# ProProject_Spherical_Robot_RC_V2_0_2024-.net
KiCad netlist of a schematic drawn in EasyEDA Pro
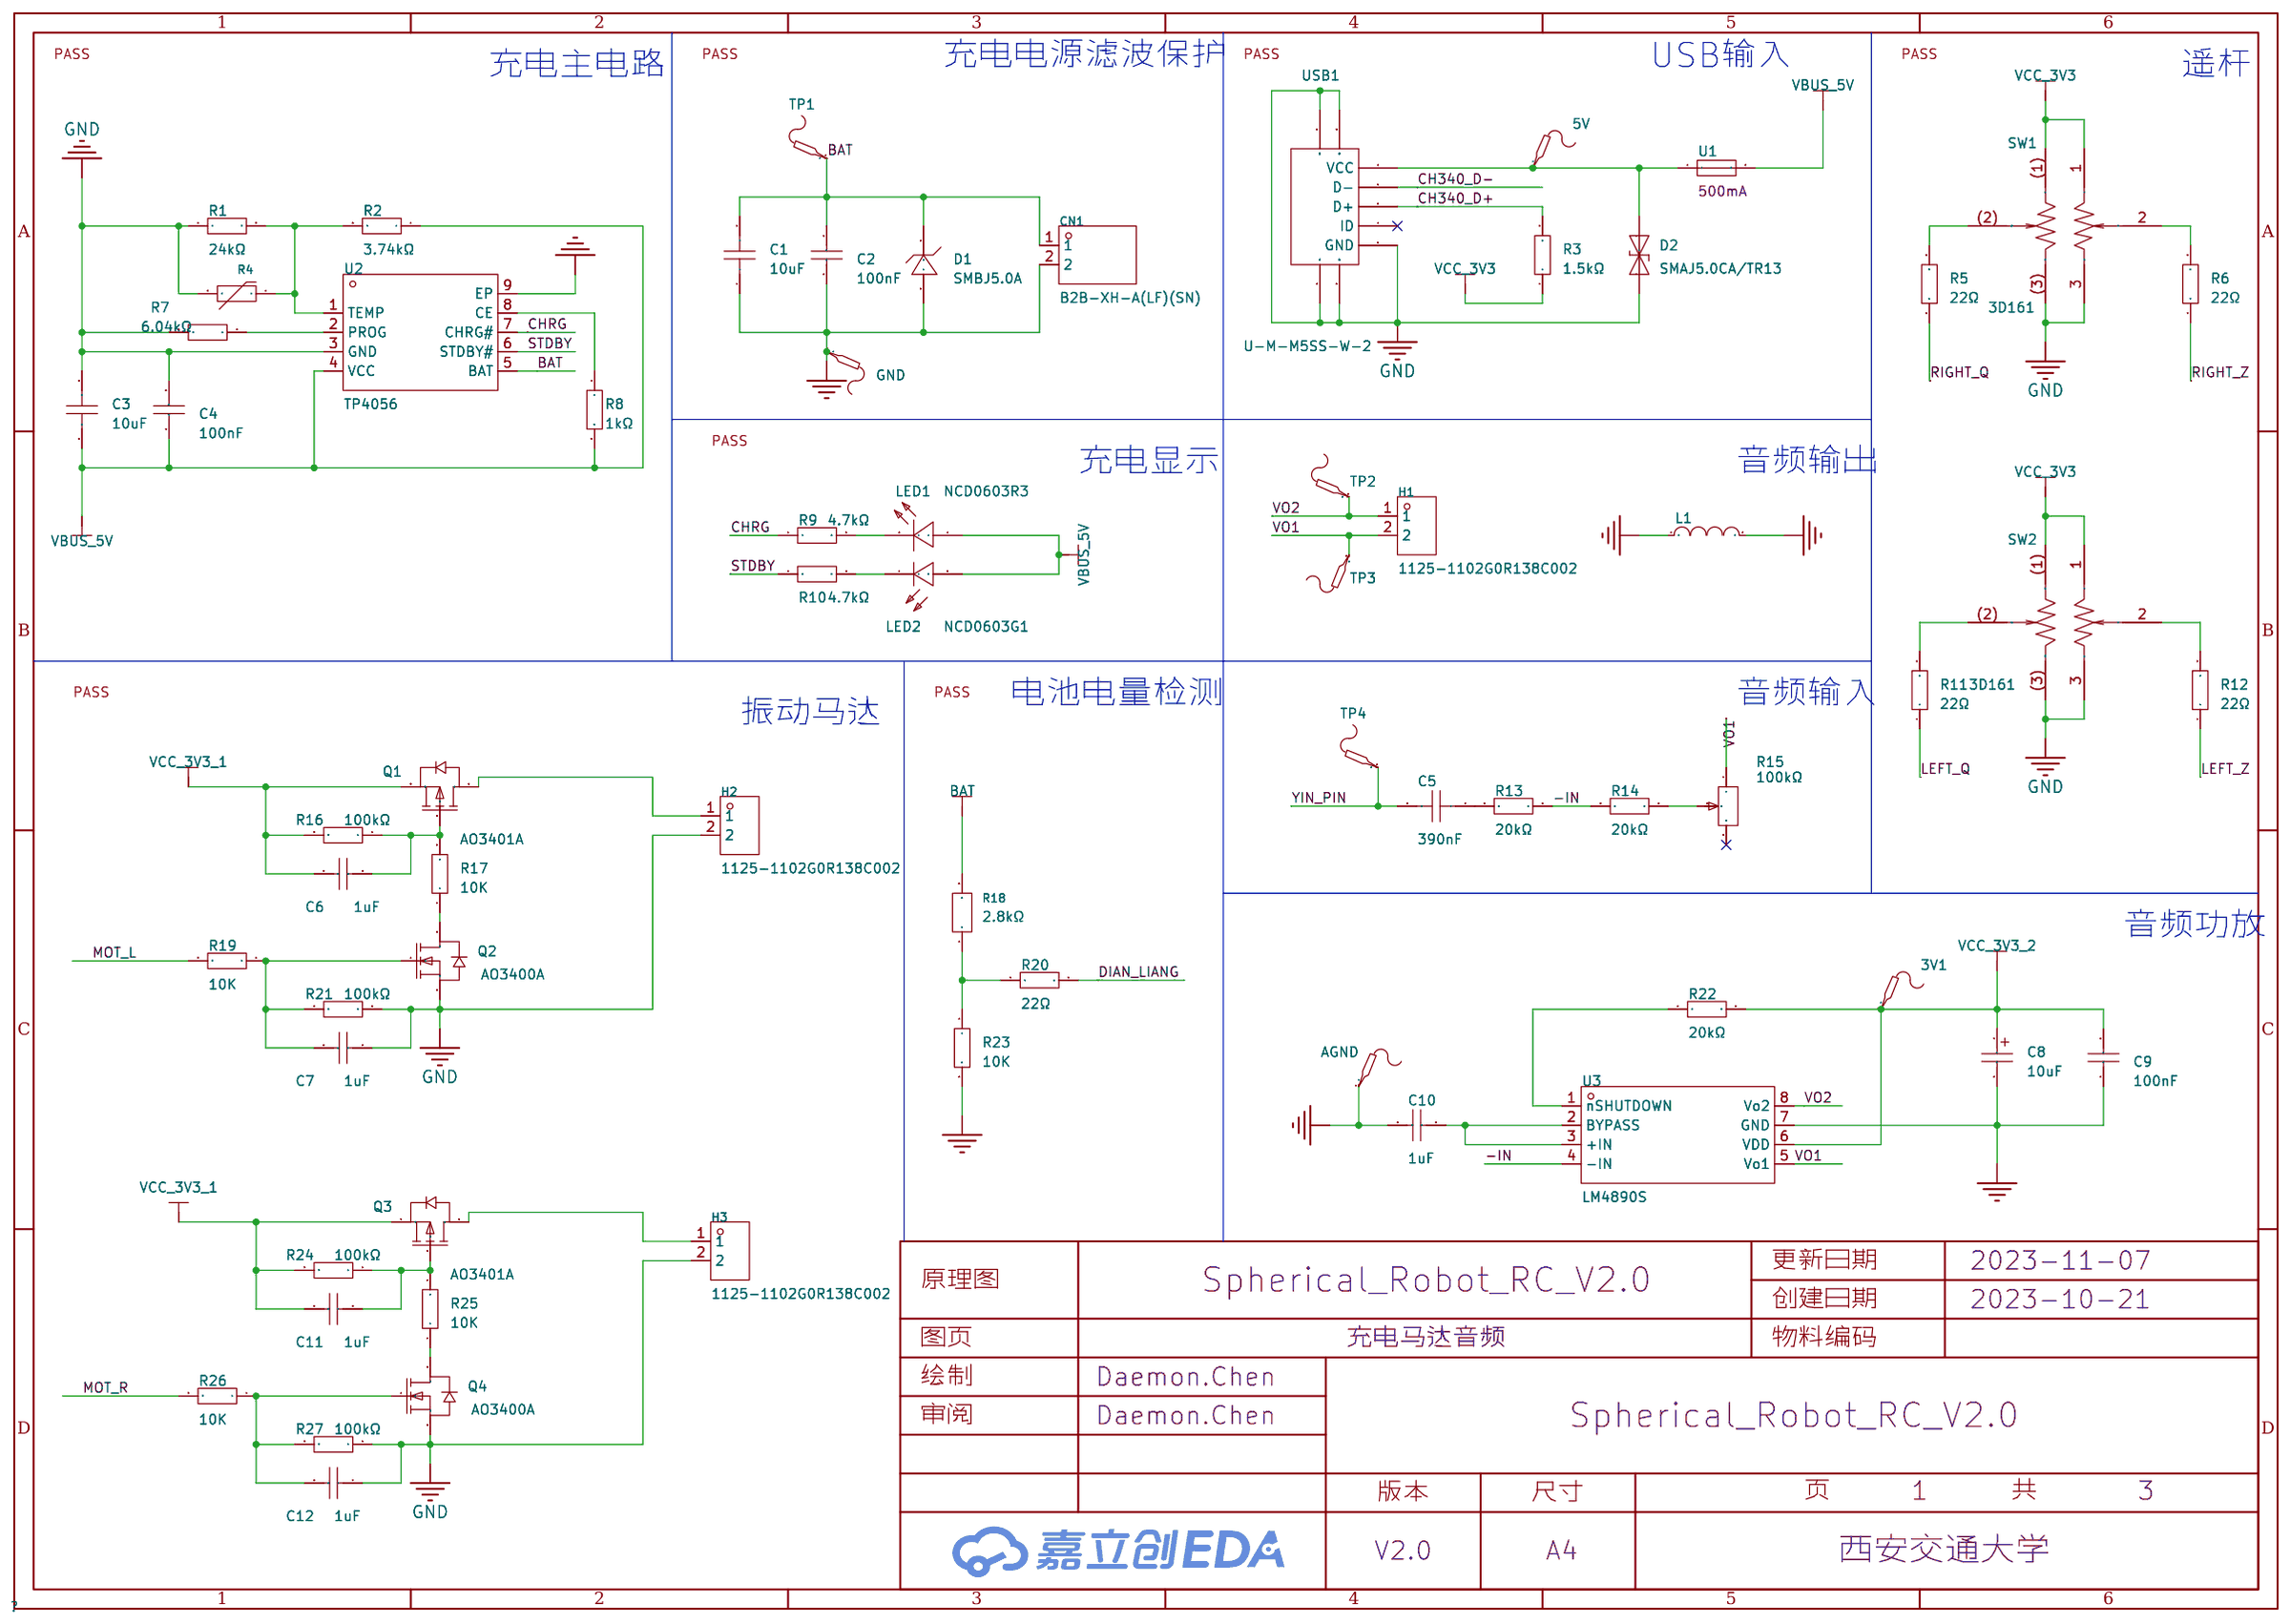
[diagram p0: 充电马达音频]
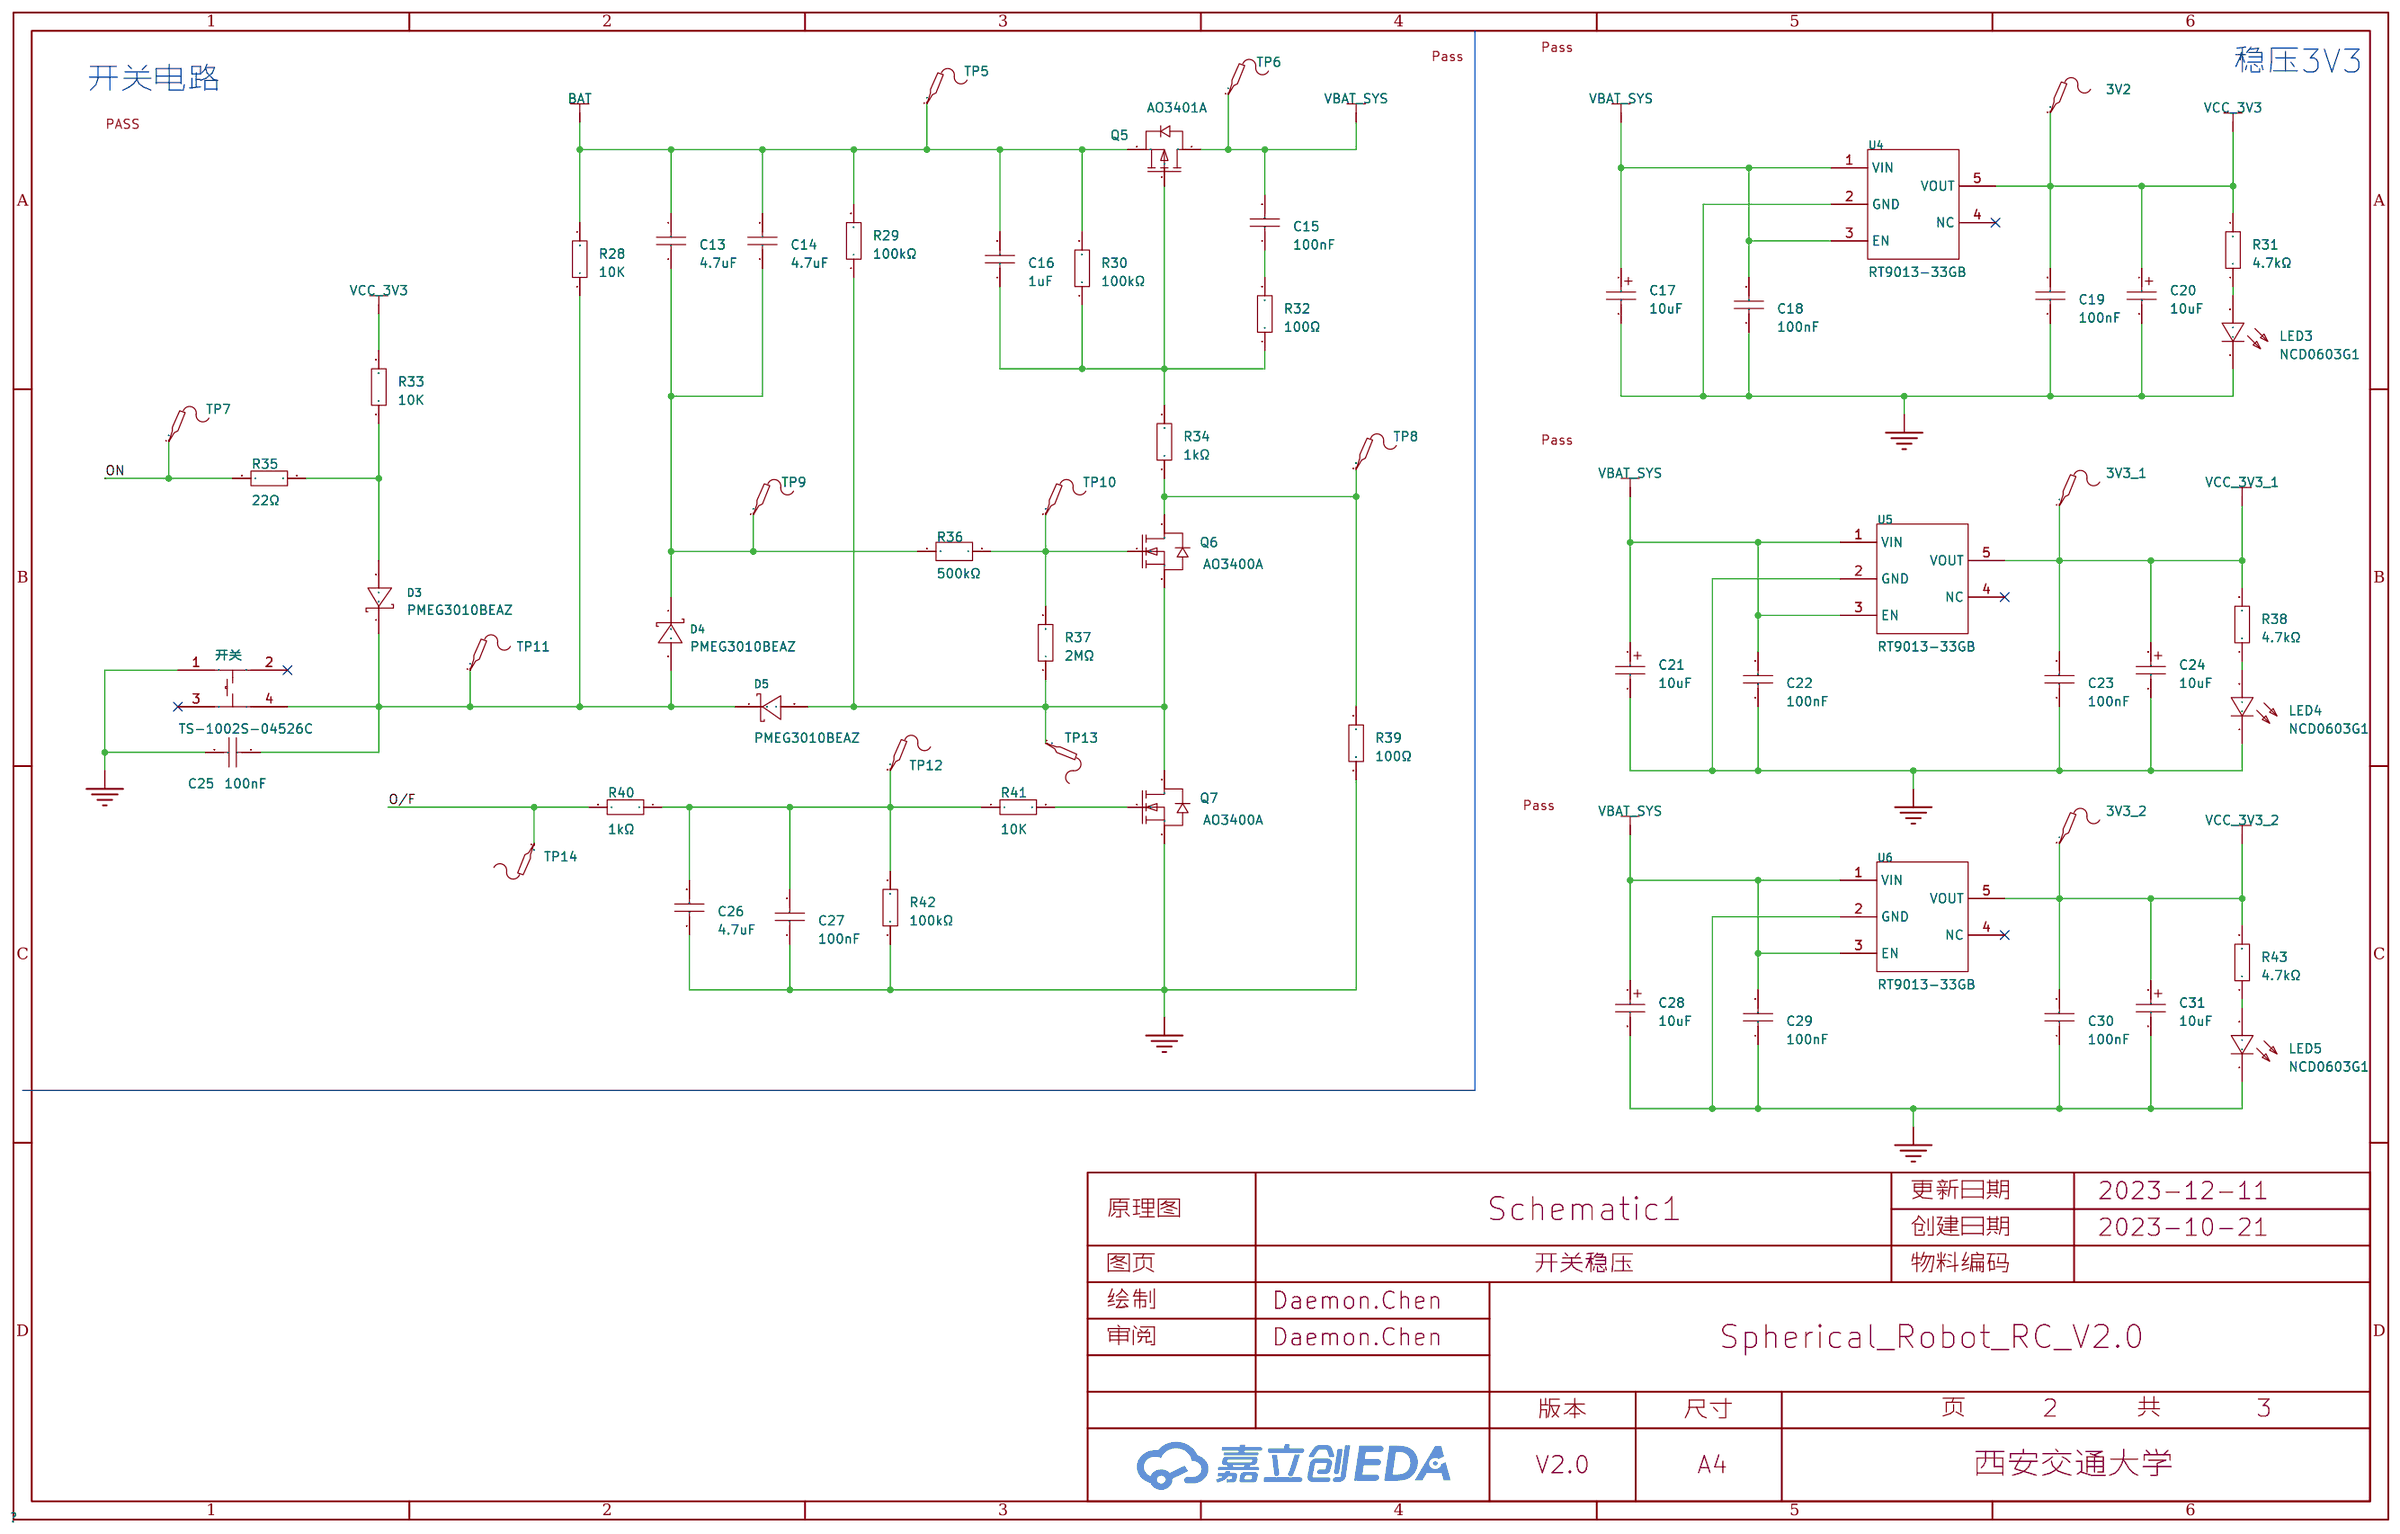
[diagram p1: 开关稳压]
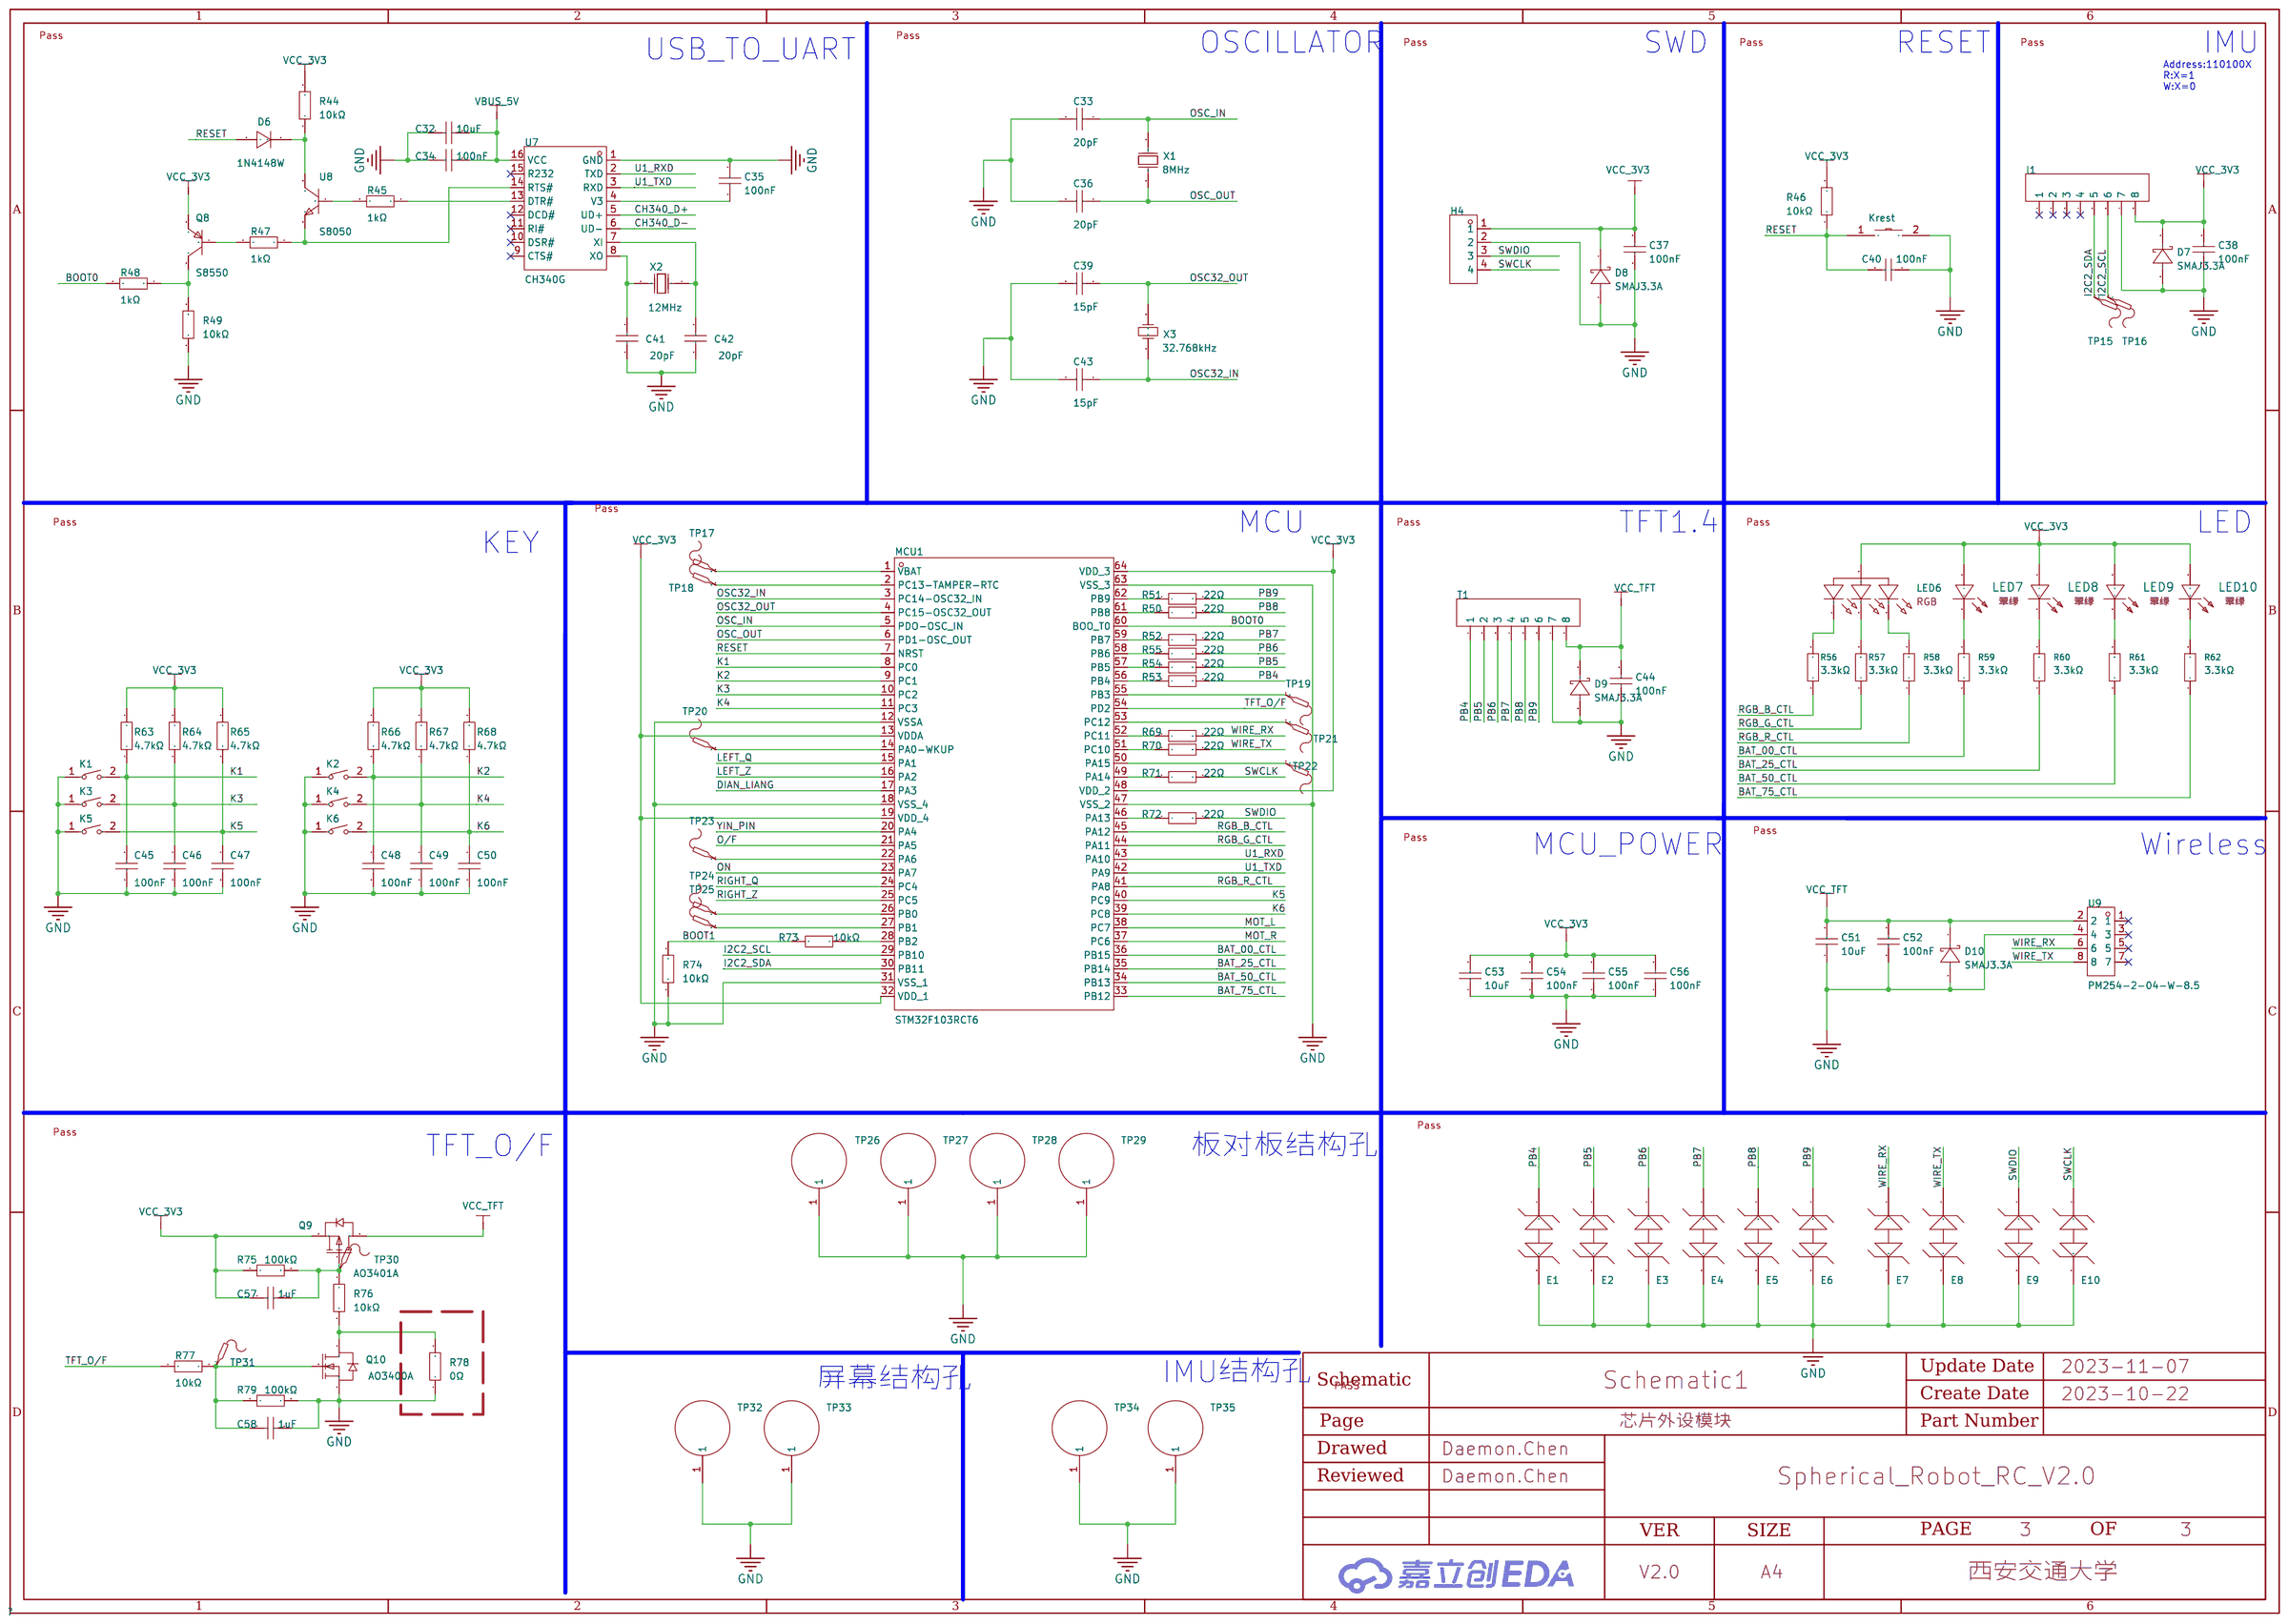
[diagram p2: 芯片外设模块]

(export (version "E")
  (design (tool "Eeschema 10.0.6"))
  (components
    (comp (ref "3V1")
      (value "~")
      (footprint "easyedapro:Test-Point-0.5mm")
      (description "Test Point 测试点")
      (libsource (lib "easyedapro") (part "Test-Point"))
    )
    (comp (ref "5V")
      (value "~")
      (footprint "easyedapro:Test-Point-0.5mm")
      (description "Test Point 测试点")
      (libsource (lib "easyedapro") (part "Test-Point"))
    )
    (comp (ref "AGND")
      (value "~")
      (footprint "easyedapro:Test-Point-0.5mm")
      (description "Test Point 测试点")
      (libsource (lib "easyedapro") (part "Test-Point"))
    )
    (comp (ref "C1")
      (value "10uF")
      (footprint "easyedapro:C0603")
      (description "容值:10uF;精度:±10%;额定电压:16V;材质(温度系数):-;")
      (fields
        (field (name "Manufacturer Part") "CL10A106KO8NQNC")
        (field (name "Manufacturer") "SAMSUNG(三星)")
      )
      (libsource (lib "easyedapro") (part "CL10A106KO8NQNC"))
    )
    (comp (ref "C2")
      (value "100nF")
      (footprint "easyedapro:C0603")
      (description "容值:100nF;精度:±10%;额定电压:16V;材质(温度系数):X7R;")
      (fields
        (field (name "Manufacturer Part") "CL10B104KO8NNNC")
        (field (name "Manufacturer") "SAMSUNG(三星)")
      )
      (libsource (lib "easyedapro") (part "CL10B104KO8NNNC"))
    )
    (comp (ref "C3")
      (value "10uF")
      (footprint "easyedapro:C0603")
      (description "容值:10uF;精度:±10%;额定电压:16V;材质(温度系数):-;")
      (fields
        (field (name "Manufacturer Part") "CL10A106KO8NQNC")
        (field (name "Manufacturer") "SAMSUNG(三星)")
      )
      (libsource (lib "easyedapro") (part "CL10A106KO8NQNC"))
    )
    (comp (ref "C4")
      (value "100nF")
      (footprint "easyedapro:C0603")
      (description "容值:100nF;精度:±10%;额定电压:16V;材质(温度系数):X7R;")
      (fields
        (field (name "Manufacturer Part") "CL10B104KO8NNNC")
        (field (name "Manufacturer") "SAMSUNG(三星)")
      )
      (libsource (lib "easyedapro") (part "CL10B104KO8NNNC"))
    )
    (comp (ref "C5")
      (value "390nF")
      (footprint "easyedapro:C0603")
      (description "容值:390nF;精度:±10%;额定电压:16V;材质(温度系数):X7R;")
      (fields
        (field (name "Manufacturer Part") "GCM188R71C394KA55D")
        (field (name "Manufacturer") "muRata(村田)")
      )
      (libsource (lib "easyedapro") (part "GCM188R71C394KA55D"))
    )
    (comp (ref "C6")
      (value "1uF")
      (footprint "easyedapro:C0603")
      (description "容值:1uF;精度:±10%;额定电压:16V;材质(温度系数):X5R;")
      (fields
        (field (name "Manufacturer Part") "CL10A105KO8NNNC")
        (field (name "Manufacturer") "SAMSUNG(三星)")
      )
      (libsource (lib "easyedapro") (part "CL10A105KO8NNNC"))
    )
    (comp (ref "C7")
      (value "1uF")
      (footprint "easyedapro:C0603")
      (description "容值:1uF;精度:±10%;额定电压:16V;材质(温度系数):X5R;")
      (fields
        (field (name "Manufacturer Part") "CL10A105KO8NNNC")
        (field (name "Manufacturer") "SAMSUNG(三星)")
      )
      (libsource (lib "easyedapro") (part "CL10A105KO8NNNC"))
    )
    (comp (ref "C8")
      (value "10uF")
      (footprint "easyedapro:CAP-SMD_L3.2-W1.6-RD")
      (description "容值:10uF;精度:±10%;额定电压:16V;等效串联电阻:10Ω@100kHz;")
      (fields
        (field (name "Manufacturer Part") "CA45-A-16V-10uF-K")
        (field (name "Manufacturer") "CEC(振华新云)")
      )
      (libsource (lib "easyedapro") (part "CA45-A-16V-10UF-K"))
    )
    (comp (ref "C9")
      (value "100nF")
      (footprint "easyedapro:C0603")
      (description "容值:100nF;精度:±10%;额定电压:16V;材质(温度系数):X7R;")
      (fields
        (field (name "Manufacturer Part") "CL10B104KO8NNNC")
        (field (name "Manufacturer") "SAMSUNG(三星)")
      )
      (libsource (lib "easyedapro") (part "CL10B104KO8NNNC"))
    )
    (comp (ref "C10")
      (value "1uF")
      (footprint "easyedapro:C0603")
      (description "容值:1uF;精度:±10%;额定电压:16V;材质(温度系数):X5R;")
      (fields
        (field (name "Manufacturer Part") "CL10A105KO8NNNC")
        (field (name "Manufacturer") "SAMSUNG(三星)")
      )
      (libsource (lib "easyedapro") (part "CL10A105KO8NNNC"))
    )
    (comp (ref "C11")
      (value "1uF")
      (footprint "easyedapro:C0603")
      (description "容值:1uF;精度:±10%;额定电压:16V;材质(温度系数):X5R;")
      (fields
        (field (name "Manufacturer Part") "CL10A105KO8NNNC")
        (field (name "Manufacturer") "SAMSUNG(三星)")
      )
      (libsource (lib "easyedapro") (part "CL10A105KO8NNNC"))
    )
    (comp (ref "C12")
      (value "1uF")
      (footprint "easyedapro:C0603")
      (description "容值:1uF;精度:±10%;额定电压:16V;材质(温度系数):X5R;")
      (fields
        (field (name "Manufacturer Part") "CL10A105KO8NNNC")
        (field (name "Manufacturer") "SAMSUNG(三星)")
      )
      (libsource (lib "easyedapro") (part "CL10A105KO8NNNC"))
    )
    (comp (ref "CN1")
      (value "B2B-XH-A(LF)(SN)")
      (footprint "easyedapro:CONN-TH_B2B-XH-A-LF-SN")
      (description "参考系列:XH;间距:2.5mm;插针结构:1x2P;排数:1;每排PIN数:2;行距:-;安装方式:-;触头材质:黄铜;")
      (fields (field (name "Manufacturer") "JST"))
      (libsource (lib "easyedapro") (part "B2B-XH-A (LF)(SN)"))
    )
    (comp (ref "D1")
      (value "SMBJ5.0A")
      (footprint "easyedapro:SMB_L4.4-W3.6-LS5.3-RD")
      (description "极性:单向;")
      (fields (field (name "Manufacturer") "TWGMC(台湾迪嘉)"))
      (libsource (lib "easyedapro") (part "SMBJ5.0A_C726811"))
    )
    (comp (ref "D2")
      (value "SMAJ5.0CA/TR13")
      (footprint "easyedapro:SMA_L4.4-W2.6-LS5.0-BI")
      (fields (field (name "Manufacturer") "Brightking(君耀电子)"))
      (libsource (lib "easyedapro") (part "SMAJ5.0CA_C78402"))
    )
    (comp (ref "GND")
      (value "~")
      (footprint "easyedapro:Test-Point-0.5mm")
      (description "Test Point 测试点")
      (libsource (lib "easyedapro") (part "Test-Point"))
    )
    (comp (ref "H1")
      (value "1125-1102G0R138C002")
      (footprint "easyedapro:HDR-TH_2P-P2.54-H-M-W7.3")
      (fields (field (name "Manufacturer") "Wcon(维峰电子)"))
      (libsource (lib "easyedapro") (part "1125-1102G0R138C002"))
    )
    (comp (ref "H2")
      (value "1125-1102G0R138C002")
      (footprint "easyedapro:HDR-TH_2P-P2.54-H-M-W7.3")
      (fields (field (name "Manufacturer") "Wcon(维峰电子)"))
      (libsource (lib "easyedapro") (part "1125-1102G0R138C002"))
    )
    (comp (ref "H3")
      (value "1125-1102G0R138C002")
      (footprint "easyedapro:HDR-TH_2P-P2.54-H-M-W7.3")
      (fields (field (name "Manufacturer") "Wcon(维峰电子)"))
      (libsource (lib "easyedapro") (part "1125-1102G0R138C002"))
    )
    (comp (ref "L1")
      (value "YI201209U121-5R0T")
      (footprint "easyedapro:L0805")
      (description "标称阻抗@测试频率:120Ω@100MHz;误差:±25%;直流电阻(RDC):30mΩ;额定电流:5A;")
      (fields (field (name "Manufacturer") "YJYCOIN(益嘉源)"))
      (libsource (lib "easyedapro") (part "YI201209U121-5R0T"))
    )
    (comp (ref "LED1")
      (value "NCD0603R3")
      (footprint "easyedapro:LED0603-R-RD_RED")
      (description "尺寸1.6x0.8x0.8；IF=20ma：1.6~2.6v，620~640nm,51~150mcd金线，光强高，功耗低，可靠性好，寿命长")
      (fields (field (name "Manufacturer") "国星光电"))
      (libsource (lib "easyedapro") (part "NCD0603R3"))
    )
    (comp (ref "LED2")
      (value "NCD0603G1")
      (footprint "easyedapro:LED0603-RD")
      (description "发光颜色:翠绿;")
      (fields (field (name "Manufacturer") "国星光电"))
      (libsource (lib "easyedapro") (part "FC-D1608UGK-520D10"))
    )
    (comp (ref "Q1")
      (value "AO3401A")
      (footprint "easyedapro:SOT-23-3_L2.9-W1.3-P1.90-LS2.4-BR")
      (fields (field (name "Manufacturer") "HUASHUO(华朔)"))
      (libsource (lib "easyedapro") (part "AO3401A_C700954"))
    )
    (comp (ref "Q2")
      (value "AO3400A")
      (footprint "easyedapro:SOT-23-3_L2.9-W1.3-P1.90-LS2.4-BR")
      (fields (field (name "Manufacturer") "HUASHUO(华朔)"))
      (libsource (lib "easyedapro") (part "AO3400A_C700953"))
    )
    (comp (ref "Q3")
      (value "AO3401A")
      (footprint "easyedapro:SOT-23-3_L2.9-W1.3-P1.90-LS2.4-BR")
      (fields (field (name "Manufacturer") "HUASHUO(华朔)"))
      (libsource (lib "easyedapro") (part "AO3401A_C700954"))
    )
    (comp (ref "Q4")
      (value "AO3400A")
      (footprint "easyedapro:SOT-23-3_L2.9-W1.3-P1.90-LS2.4-BR")
      (fields (field (name "Manufacturer") "HUASHUO(华朔)"))
      (libsource (lib "easyedapro") (part "AO3400A_C700953"))
    )
    (comp (ref "R1")
      (value "24kΩ")
      (footprint "easyedapro:R0603")
      (description "电阻类型:厚膜电阻;阻值:24kΩ;精度:±1%;功率:100mW;")
      (fields
        (field (name "Manufacturer Part") "0603WAF2402T5E")
        (field (name "Manufacturer") "UNI-ROYAL(厚声)")
      )
      (libsource (lib "easyedapro") (part "0603WAF2402T5E"))
    )
    (comp (ref "R2")
      (value "3.74kΩ")
      (footprint "easyedapro:R0603")
      (description "电阻类型:厚膜电阻;阻值:3.74kΩ;精度:±1%;功率:100mW;")
      (fields (field (name "Manufacturer Part") "RTT033741FTP") (field (name "Manufacturer") "RALEC(旺诠)"))
      (libsource (lib "easyedapro") (part "RTT033741FTP"))
    )
    (comp (ref "R3")
      (value "1.5kΩ")
      (footprint "easyedapro:R0603")
      (description "阻值:1.5kΩ;精度:±1%;温度系数:±100ppm/℃;功率:1/10W;最大工作电压:75V;工作温度范围:-55℃~+155℃;")
      (fields
        (field (name "Manufacturer Part") "0603WAF1501T5E")
        (field (name "Manufacturer") "UNI-ROYAL(厚声)")
      )
      (libsource (lib "easyedapro") (part "0603WAF1501T5E"))
    )
    (comp (ref "R4")
      (value "NCP18XH103F03RB")
      (footprint "easyedapro:R0603")
      (fields (field (name "Manufacturer") "muRata(村田)"))
      (libsource (lib "easyedapro") (part "NCP18XH103F03RB"))
    )
    (comp (ref "R5")
      (value "22Ω")
      (fields
        (field (name "Manufacturer Part") "0603WAF220JT5E")
        (field (name "Manufacturer") "UNI-ROYAL(厚声)")
      )
      (libsource (lib "easyedapro") (part "0603WAF220JT5E"))
    )
    (comp (ref "R6")
      (value "22Ω")
      (fields
        (field (name "Manufacturer Part") "0603WAF220JT5E")
        (field (name "Manufacturer") "UNI-ROYAL(厚声)")
      )
      (libsource (lib "easyedapro") (part "0603WAF220JT5E"))
    )
    (comp (ref "R7")
      (value "6.04kΩ")
      (footprint "easyedapro:R0603")
      (description "阻值:6.04kΩ;精度:±1%;功率:100mW;")
      (fields
        (field (name "Manufacturer Part") "RMC06036.04K1%N")
        (field (name "Manufacturer") "Tyohm(幸亚电阻)")
      )
      (libsource (lib "easyedapro") (part "RMC06036.04K1%N"))
    )
    (comp (ref "R8")
      (value "1kΩ")
      (footprint "easyedapro:R0603")
      (description "电阻类型:厚膜电阻;阻值:1kΩ;精度:±1%;功率:100mW;")
      (fields
        (field (name "Manufacturer Part") "0603WAF1001T5E")
        (field (name "Manufacturer") "UNI-ROYAL(厚声)")
      )
      (libsource (lib "easyedapro") (part "0603WAF1001T5E"))
    )
    (comp (ref "R9")
      (value "4.7kΩ")
      (footprint "easyedapro:R0603")
      (description "电阻类型:厚膜电阻;阻值:4.7kΩ;精度:±1%;功率:100mW;")
      (fields
        (field (name "Manufacturer Part") "0603WAF4701T5E")
        (field (name "Manufacturer") "UNI-ROYAL(厚声)")
      )
      (libsource (lib "easyedapro") (part "0603WAF4701T5E"))
    )
    (comp (ref "R10")
      (value "4.7kΩ")
      (footprint "easyedapro:R0603")
      (description "电阻类型:厚膜电阻;阻值:4.7kΩ;精度:±1%;功率:100mW;")
      (fields
        (field (name "Manufacturer Part") "0603WAF4701T5E")
        (field (name "Manufacturer") "UNI-ROYAL(厚声)")
      )
      (libsource (lib "easyedapro") (part "0603WAF4701T5E"))
    )
    (comp (ref "R11")
      (value "22Ω")
      (fields
        (field (name "Manufacturer Part") "0603WAF220JT5E")
        (field (name "Manufacturer") "UNI-ROYAL(厚声)")
      )
      (libsource (lib "easyedapro") (part "0603WAF220JT5E"))
    )
    (comp (ref "R12")
      (value "22Ω")
      (fields
        (field (name "Manufacturer Part") "0603WAF220JT5E")
        (field (name "Manufacturer") "UNI-ROYAL(厚声)")
      )
      (libsource (lib "easyedapro") (part "0603WAF220JT5E"))
    )
    (comp (ref "R13")
      (value "20kΩ")
      (footprint "easyedapro:R0603")
      (description "电阻类型:厚膜电阻;阻值:20kΩ;精度:±1%;功率:100mW;")
      (fields
        (field (name "Manufacturer Part") "0603WAF2002T5E")
        (field (name "Manufacturer") "UNI-ROYAL(厚声)")
      )
      (libsource (lib "easyedapro") (part "0603WAF2002T5E"))
    )
    (comp (ref "R14")
      (value "20kΩ")
      (footprint "easyedapro:R0603")
      (description "电阻类型:厚膜电阻;阻值:20kΩ;精度:±1%;功率:100mW;")
      (fields
        (field (name "Manufacturer Part") "0603WAF2002T5E")
        (field (name "Manufacturer") "UNI-ROYAL(厚声)")
      )
      (libsource (lib "easyedapro") (part "0603WAF2002T5E"))
    )
    (comp (ref "R15")
      (value "100kΩ")
      (footprint "easyedapro:RES-ADJ-TH_3296W")
      (description "阻值:100kΩ;精度:±10%;")
      (fields (field (name "Manufacturer Part") "3296W-1-104LF") (field (name "Manufacturer") "BOURNS"))
      (libsource (lib "easyedapro") (part "3296W-1-104LF"))
    )
    (comp (ref "R16")
      (value "100kΩ")
      (footprint "easyedapro:R0603")
      (description "电阻类型:厚膜电阻;阻值:100kΩ;精度:±1%;功率:100mW;")
      (fields
        (field (name "Manufacturer Part") "0603WAF1003T5E")
        (field (name "Manufacturer") "UNI-ROYAL(厚声)")
      )
      (libsource (lib "easyedapro") (part "0603WAF1003T5E"))
    )
    (comp (ref "R17") (value "10K") (footprint "easyedapro:R0603") (libsource (lib "easyedapro") (part "电阻")))
    (comp (ref "R18")
      (value "2.8kΩ")
      (footprint "easyedapro:R0603")
      (description "电阻类型:厚膜电阻;阻值:2.8kΩ;精度:±1%;功率:100mW;温度系数:±100ppm/°C;")
      (fields (field (name "Manufacturer Part") "FRC0603F2801TS") (field (name "Manufacturer") "FOJAN(富捷)"))
      (libsource (lib "easyedapro") (part "FRC0603F2801TS"))
    )
    (comp (ref "R19") (value "10K") (footprint "easyedapro:R0603") (libsource (lib "easyedapro") (part "电阻")))
    (comp (ref "R20")
      (value "22Ω")
      (fields
        (field (name "Manufacturer Part") "0603WAF220JT5E")
        (field (name "Manufacturer") "UNI-ROYAL(厚声)")
      )
      (libsource (lib "easyedapro") (part "0603WAF220JT5E"))
    )
    (comp (ref "R21")
      (value "100kΩ")
      (footprint "easyedapro:R0603")
      (description "电阻类型:厚膜电阻;阻值:100kΩ;精度:±1%;功率:100mW;")
      (fields
        (field (name "Manufacturer Part") "0603WAF1003T5E")
        (field (name "Manufacturer") "UNI-ROYAL(厚声)")
      )
      (libsource (lib "easyedapro") (part "0603WAF1003T5E"))
    )
    (comp (ref "R22")
      (value "20kΩ")
      (footprint "easyedapro:R0603")
      (description "电阻类型:厚膜电阻;阻值:20kΩ;精度:±1%;功率:100mW;")
      (fields
        (field (name "Manufacturer Part") "0603WAF2002T5E")
        (field (name "Manufacturer") "UNI-ROYAL(厚声)")
      )
      (libsource (lib "easyedapro") (part "0603WAF2002T5E"))
    )
    (comp (ref "R23") (value "10K") (footprint "easyedapro:R0603") (libsource (lib "easyedapro") (part "电阻")))
    (comp (ref "R24")
      (value "100kΩ")
      (footprint "easyedapro:R0603")
      (description "电阻类型:厚膜电阻;阻值:100kΩ;精度:±1%;功率:100mW;")
      (fields
        (field (name "Manufacturer Part") "0603WAF1003T5E")
        (field (name "Manufacturer") "UNI-ROYAL(厚声)")
      )
      (libsource (lib "easyedapro") (part "0603WAF1003T5E"))
    )
    (comp (ref "R25") (value "10K") (footprint "easyedapro:R0603") (libsource (lib "easyedapro") (part "电阻")))
    (comp (ref "R26") (value "10K") (footprint "easyedapro:R0603") (libsource (lib "easyedapro") (part "电阻")))
    (comp (ref "R27")
      (value "100kΩ")
      (footprint "easyedapro:R0603")
      (description "电阻类型:厚膜电阻;阻值:100kΩ;精度:±1%;功率:100mW;")
      (fields
        (field (name "Manufacturer Part") "0603WAF1003T5E")
        (field (name "Manufacturer") "UNI-ROYAL(厚声)")
      )
      (libsource (lib "easyedapro") (part "0603WAF1003T5E"))
    )
    (comp (ref "SW1")
      (value "3D161")
      (footprint "easyedapro:SW-TH_3D161")
      (description "摇杆  多向")
      (fields (field (name "Manufacturer") "韩国韩荣"))
      (libsource (lib "easyedapro") (part "3D161"))
    )
    (comp (ref "SW2")
      (value "3D161")
      (footprint "easyedapro:SW-TH_3D161")
      (description "摇杆  多向")
      (fields (field (name "Manufacturer") "韩国韩荣"))
      (libsource (lib "easyedapro") (part "3D161"))
    )
    (comp (ref "TP1")
      (value "~")
      (footprint "easyedapro:Test-Point-0.5mm")
      (description "Test Point 测试点")
      (libsource (lib "easyedapro") (part "Test-Point"))
    )
    (comp (ref "TP2")
      (value "~")
      (footprint "easyedapro:Test-Point-0.5mm")
      (description "Test Point 测试点")
      (libsource (lib "easyedapro") (part "Test-Point"))
    )
    (comp (ref "TP3")
      (value "~")
      (footprint "easyedapro:Test-Point-0.5mm")
      (description "Test Point 测试点")
      (libsource (lib "easyedapro") (part "Test-Point"))
    )
    (comp (ref "TP4")
      (value "~")
      (footprint "easyedapro:Test-Point-0.5mm")
      (description "Test Point 测试点")
      (libsource (lib "easyedapro") (part "Test-Point"))
    )
    (comp (ref "U1")
      (value "SMD0805B050TF")
      (footprint "easyedapro:F0805")
      (description "最大电压:6V;最大电流:100A;保持电流:500mA;跳闸电流:1A;最大动作时间:100ms;")
      (fields (field (name "Manufacturer") "Brightking(君耀电子)") (field (name "Hold Current") "500mA"))
      (libsource (lib "easyedapro") (part "SMD0805B050TF"))
    )
    (comp (ref "U2")
      (value "TP4056")
      (footprint "easyedapro:ESOP-8_L4.9-W3.9-P1.27-LS6.0-BL-EP")
      (fields (field (name "Manufacturer") "UMW(友台半导体)"))
      (libsource (lib "easyedapro") (part "TP4056_C725790"))
    )
    (comp (ref "U3")
      (value "LM4890S")
      (footprint "easyedapro:MSOP-8_L3.0-W3.0-P0.65-LS5.0-BL")
      (description "功放类型:-;输出功率:-;")
      (fields (field (name "Manufacturer") "IDCHIP(英锐芯)"))
      (libsource (lib "easyedapro") (part "LM4890S_C329452"))
    )
    (comp (ref "USB1")
      (value "U-M-M5SS-W-2")
      (footprint "easyedapro:MICRO-USB-SMD_MICRO-USB-13")
      (description "连接器类型:Mini-B;标准:USB 2;公母:母座;触点数量:5;端口数量:1;")
      (fields (field (name "Manufacturer") "韩国韩荣"))
      (libsource (lib "easyedapro") (part "u-m-m5ss-w-2"))
    )
    (comp (ref "3V2")
      (value "~")
      (footprint "easyedapro:Test-Point-0.5mm")
      (description "Test Point 测试点")
      (libsource (lib "easyedapro") (part "Test-Point"))
    )
    (comp (ref "3V3_1")
      (value "~")
      (footprint "easyedapro:Test-Point-0.5mm")
      (description "Test Point 测试点")
      (libsource (lib "easyedapro") (part "Test-Point"))
    )
    (comp (ref "3V3_2")
      (value "~")
      (footprint "easyedapro:Test-Point-0.5mm")
      (description "Test Point 测试点")
      (libsource (lib "easyedapro") (part "Test-Point"))
    )
    (comp (ref "C13")
      (value "4.7uF")
      (footprint "easyedapro:C0603")
      (description "容值:4.7uF;精度:±10%;额定电压:16V;材质(温度系数):X5R;")
      (fields
        (field (name "Manufacturer Part") "CL10A475KO8NNNC")
        (field (name "Manufacturer") "SAMSUNG(三星)")
      )
      (libsource (lib "easyedapro") (part "CL10A475KO8NNNC"))
    )
    (comp (ref "C14")
      (value "4.7uF")
      (footprint "easyedapro:C0603")
      (description "容值:4.7uF;精度:±10%;额定电压:16V;材质(温度系数):X5R;")
      (fields
        (field (name "Manufacturer Part") "CL10A475KO8NNNC")
        (field (name "Manufacturer") "SAMSUNG(三星)")
      )
      (libsource (lib "easyedapro") (part "CL10A475KO8NNNC"))
    )
    (comp (ref "C15")
      (value "100nF")
      (footprint "easyedapro:C0603")
      (description "容值:100nF;精度:±10%;额定电压:16V;材质(温度系数):X7R;")
      (fields
        (field (name "Manufacturer Part") "CL10B104KO8NNNC")
        (field (name "Manufacturer") "SAMSUNG(三星)")
      )
      (libsource (lib "easyedapro") (part "CL10B104KO8NNNC"))
    )
    (comp (ref "C16")
      (value "1uF")
      (footprint "easyedapro:C0603")
      (description "容值:1uF;精度:±10%;额定电压:16V;材质(温度系数):X5R;")
      (fields
        (field (name "Manufacturer Part") "CL10A105KO8NNNC")
        (field (name "Manufacturer") "SAMSUNG(三星)")
      )
      (libsource (lib "easyedapro") (part "CL10A105KO8NNNC"))
    )
    (comp (ref "C17")
      (value "10uF")
      (footprint "easyedapro:CAP-SMD_L3.2-W1.6-RD")
      (description "容值:10uF;精度:±10%;额定电压:16V;等效串联电阻:10Ω@100kHz;")
      (fields
        (field (name "Manufacturer Part") "CA45-A-16V-10uF-K")
        (field (name "Manufacturer") "CEC(振华新云)")
      )
      (libsource (lib "easyedapro") (part "CA45-A-16V-10UF-K"))
    )
    (comp (ref "C18")
      (value "100nF")
      (footprint "easyedapro:C0603")
      (description "容值:100nF;精度:±10%;额定电压:16V;材质(温度系数):X7R;")
      (fields
        (field (name "Manufacturer Part") "CL10B104KO8NNNC")
        (field (name "Manufacturer") "SAMSUNG(三星)")
      )
      (libsource (lib "easyedapro") (part "CL10B104KO8NNNC"))
    )
    (comp (ref "C19")
      (value "100nF")
      (footprint "easyedapro:C0603")
      (description "容值:100nF;精度:±10%;额定电压:16V;材质(温度系数):X7R;")
      (fields
        (field (name "Manufacturer Part") "CL10B104KO8NNNC")
        (field (name "Manufacturer") "SAMSUNG(三星)")
      )
      (libsource (lib "easyedapro") (part "CL10B104KO8NNNC"))
    )
    (comp (ref "C20")
      (value "10uF")
      (footprint "easyedapro:CAP-SMD_L3.2-W1.6-RD")
      (description "容值:10uF;精度:±10%;额定电压:16V;等效串联电阻:10Ω@100kHz;")
      (fields
        (field (name "Manufacturer Part") "CA45-A-16V-10uF-K")
        (field (name "Manufacturer") "CEC(振华新云)")
      )
      (libsource (lib "easyedapro") (part "CA45-A-16V-10UF-K"))
    )
    (comp (ref "C21")
      (value "10uF")
      (footprint "easyedapro:CAP-SMD_L3.2-W1.6-RD")
      (description "容值:10uF;精度:±10%;额定电压:16V;等效串联电阻:10Ω@100kHz;")
      (fields
        (field (name "Manufacturer Part") "CA45-A-16V-10uF-K")
        (field (name "Manufacturer") "CEC(振华新云)")
      )
      (libsource (lib "easyedapro") (part "CA45-A-16V-10UF-K"))
    )
    (comp (ref "C22")
      (value "100nF")
      (footprint "easyedapro:C0603")
      (description "容值:100nF;精度:±10%;额定电压:16V;材质(温度系数):X7R;")
      (fields
        (field (name "Manufacturer Part") "CL10B104KO8NNNC")
        (field (name "Manufacturer") "SAMSUNG(三星)")
      )
      (libsource (lib "easyedapro") (part "CL10B104KO8NNNC"))
    )
    (comp (ref "C23")
      (value "100nF")
      (footprint "easyedapro:C0603")
      (description "容值:100nF;精度:±10%;额定电压:16V;材质(温度系数):X7R;")
      (fields
        (field (name "Manufacturer Part") "CL10B104KO8NNNC")
        (field (name "Manufacturer") "SAMSUNG(三星)")
      )
      (libsource (lib "easyedapro") (part "CL10B104KO8NNNC"))
    )
    (comp (ref "C24")
      (value "10uF")
      (footprint "easyedapro:CAP-SMD_L3.2-W1.6-RD")
      (description "容值:10uF;精度:±10%;额定电压:16V;等效串联电阻:10Ω@100kHz;")
      (fields
        (field (name "Manufacturer Part") "CA45-A-16V-10uF-K")
        (field (name "Manufacturer") "CEC(振华新云)")
      )
      (libsource (lib "easyedapro") (part "CA45-A-16V-10UF-K"))
    )
    (comp (ref "C25")
      (value "100nF")
      (footprint "easyedapro:C0603")
      (description "容值:100nF;精度:±10%;额定电压:16V;材质(温度系数):X7R;")
      (fields
        (field (name "Manufacturer Part") "CL10B104KO8NNNC")
        (field (name "Manufacturer") "SAMSUNG(三星)")
      )
      (libsource (lib "easyedapro") (part "CL10B104KO8NNNC"))
    )
    (comp (ref "C26")
      (value "4.7uF")
      (footprint "easyedapro:C0603")
      (description "容值:4.7uF;精度:±10%;额定电压:16V;材质(温度系数):X5R;")
      (fields
        (field (name "Manufacturer Part") "CL10A475KO8NNNC")
        (field (name "Manufacturer") "SAMSUNG(三星)")
      )
      (libsource (lib "easyedapro") (part "CL10A475KO8NNNC"))
    )
    (comp (ref "C27")
      (value "100nF")
      (footprint "easyedapro:C0603")
      (description "容值:100nF;精度:±10%;额定电压:16V;材质(温度系数):X7R;")
      (fields
        (field (name "Manufacturer Part") "CL10B104KO8NNNC")
        (field (name "Manufacturer") "SAMSUNG(三星)")
      )
      (libsource (lib "easyedapro") (part "CL10B104KO8NNNC"))
    )
    (comp (ref "C28")
      (value "10uF")
      (footprint "easyedapro:CAP-SMD_L3.2-W1.6-RD")
      (description "容值:10uF;精度:±10%;额定电压:16V;等效串联电阻:10Ω@100kHz;")
      (fields
        (field (name "Manufacturer Part") "CA45-A-16V-10uF-K")
        (field (name "Manufacturer") "CEC(振华新云)")
      )
      (libsource (lib "easyedapro") (part "CA45-A-16V-10UF-K"))
    )
    (comp (ref "C29")
      (value "100nF")
      (footprint "easyedapro:C0603")
      (description "容值:100nF;精度:±10%;额定电压:16V;材质(温度系数):X7R;")
      (fields
        (field (name "Manufacturer Part") "CL10B104KO8NNNC")
        (field (name "Manufacturer") "SAMSUNG(三星)")
      )
      (libsource (lib "easyedapro") (part "CL10B104KO8NNNC"))
    )
    (comp (ref "C30")
      (value "100nF")
      (footprint "easyedapro:C0603")
      (description "容值:100nF;精度:±10%;额定电压:16V;材质(温度系数):X7R;")
      (fields
        (field (name "Manufacturer Part") "CL10B104KO8NNNC")
        (field (name "Manufacturer") "SAMSUNG(三星)")
      )
      (libsource (lib "easyedapro") (part "CL10B104KO8NNNC"))
    )
    (comp (ref "C31")
      (value "10uF")
      (footprint "easyedapro:CAP-SMD_L3.2-W1.6-RD")
      (description "容值:10uF;精度:±10%;额定电压:16V;等效串联电阻:10Ω@100kHz;")
      (fields
        (field (name "Manufacturer Part") "CA45-A-16V-10uF-K")
        (field (name "Manufacturer") "CEC(振华新云)")
      )
      (libsource (lib "easyedapro") (part "CA45-A-16V-10UF-K"))
    )
    (comp (ref "D3")
      (value "PMEG3010BEAZ")
      (footprint "easyedapro:SOD-323_L1.8-W1.3-LS2.5-RD")
      (description "直流反向耐压(Vr):30V;平均整流电流(Io):1A;正向压降(Vf):560mV@1A;")
      (fields (field (name "Manufacturer") "Nexperia(安世)"))
      (libsource (lib "easyedapro") (part "PMEG3010BEAZ"))
    )
    (comp (ref "D4")
      (value "PMEG3010BEAZ")
      (footprint "easyedapro:SOD-323_L1.8-W1.3-LS2.5-RD")
      (description "直流反向耐压(Vr):30V;平均整流电流(Io):1A;正向压降(Vf):560mV@1A;")
      (fields (field (name "Manufacturer") "Nexperia(安世)"))
      (libsource (lib "easyedapro") (part "PMEG3010BEAZ"))
    )
    (comp (ref "D5")
      (value "PMEG3010BEAZ")
      (footprint "easyedapro:SOD-323_L1.8-W1.3-LS2.5-RD")
      (description "直流反向耐压(Vr):30V;平均整流电流(Io):1A;正向压降(Vf):560mV@1A;")
      (fields (field (name "Manufacturer") "Nexperia(安世)"))
      (libsource (lib "easyedapro") (part "PMEG3010BEAZ"))
    )
    (comp (ref "LED3")
      (value "NCD0603G1")
      (footprint "easyedapro:LED0603-RD")
      (description "发光颜色:翠绿;")
      (fields (field (name "Manufacturer") "国星光电"))
      (libsource (lib "easyedapro") (part "FC-D1608UGK-520D10"))
    )
    (comp (ref "LED4")
      (value "NCD0603G1")
      (footprint "easyedapro:LED0603-RD")
      (description "发光颜色:翠绿;")
      (fields (field (name "Manufacturer") "国星光电"))
      (libsource (lib "easyedapro") (part "FC-D1608UGK-520D10"))
    )
    (comp (ref "LED5")
      (value "NCD0603G1")
      (footprint "easyedapro:LED0603-RD")
      (description "发光颜色:翠绿;")
      (fields (field (name "Manufacturer") "国星光电"))
      (libsource (lib "easyedapro") (part "FC-D1608UGK-520D10"))
    )
    (comp (ref "Q5")
      (value "AO3401A")
      (footprint "easyedapro:SOT-23-3_L2.9-W1.3-P1.90-LS2.4-BR")
      (fields (field (name "Manufacturer") "HUASHUO(华朔)"))
      (libsource (lib "easyedapro") (part "AO3401A_C700954"))
    )
    (comp (ref "Q6")
      (value "AO3400A")
      (footprint "easyedapro:SOT-23-3_L2.9-W1.3-P1.90-LS2.4-BR")
      (fields (field (name "Manufacturer") "HUASHUO(华朔)"))
      (libsource (lib "easyedapro") (part "AO3400A_C700953"))
    )
    (comp (ref "Q7")
      (value "AO3400A")
      (footprint "easyedapro:SOT-23-3_L2.9-W1.3-P1.90-LS2.4-BR")
      (fields (field (name "Manufacturer") "HUASHUO(华朔)"))
      (libsource (lib "easyedapro") (part "AO3400A_C700953"))
    )
    (comp (ref "R28") (value "10K") (footprint "easyedapro:R0603") (libsource (lib "easyedapro") (part "电阻")))
    (comp (ref "R29")
      (value "100kΩ")
      (footprint "easyedapro:R0603")
      (description "电阻类型:厚膜电阻;阻值:100kΩ;精度:±1%;功率:100mW;")
      (fields
        (field (name "Manufacturer Part") "0603WAF1003T5E")
        (field (name "Manufacturer") "UNI-ROYAL(厚声)")
      )
      (libsource (lib "easyedapro") (part "0603WAF1003T5E"))
    )
    (comp (ref "R30")
      (value "100kΩ")
      (footprint "easyedapro:R0603")
      (description "电阻类型:厚膜电阻;阻值:100kΩ;精度:±1%;功率:100mW;")
      (fields
        (field (name "Manufacturer Part") "0603WAF1003T5E")
        (field (name "Manufacturer") "UNI-ROYAL(厚声)")
      )
      (libsource (lib "easyedapro") (part "0603WAF1003T5E"))
    )
    (comp (ref "R31")
      (value "4.7kΩ")
      (footprint "easyedapro:R0603")
      (description "电阻类型:厚膜电阻;阻值:4.7kΩ;精度:±1%;功率:100mW;")
      (fields
        (field (name "Manufacturer Part") "0603WAF4701T5E")
        (field (name "Manufacturer") "UNI-ROYAL(厚声)")
      )
      (libsource (lib "easyedapro") (part "0603WAF4701T5E"))
    )
    (comp (ref "R32")
      (value "100Ω")
      (footprint "easyedapro:R0603")
      (description "电阻类型:厚膜电阻;阻值:100Ω;精度:±1%;功率:100mW;")
      (fields
        (field (name "Manufacturer Part") "0603WAF1000T5E")
        (field (name "Manufacturer") "UNI-ROYAL(厚声)")
      )
      (libsource (lib "easyedapro") (part "0603WAF1000T5E"))
    )
    (comp (ref "R33") (value "10K") (footprint "easyedapro:R0603") (libsource (lib "easyedapro") (part "电阻")))
    (comp (ref "R34")
      (value "1kΩ")
      (footprint "easyedapro:R0603")
      (description "电阻类型:厚膜电阻;阻值:1kΩ;精度:±1%;功率:100mW;温度系数:±100ppm/°C;最大工作电压:75V;工作温度范围:-55°C~+155°C;")
      (fields
        (field (name "Manufacturer Part") "0603WAF1001T5E")
        (field (name "Manufacturer") "UNI-ROYAL(厚声)")
      )
      (libsource (lib "easyedapro") (part "0603WAF1001T5E"))
    )
    (comp (ref "R35")
      (value "22Ω")
      (footprint "easyedapro:R0603")
      (fields
        (field (name "Manufacturer Part") "0603WAF220JT5E")
        (field (name "Manufacturer") "UNI-ROYAL(厚声)")
      )
      (libsource (lib "easyedapro") (part "电阻"))
    )
    (comp (ref "R36")
      (value "500kΩ")
      (footprint "easyedapro:R0603")
      (description "电阻类型:薄膜电阻;阻值:500kΩ;精度:±0.1%;功率:100mW;")
      (fields (field (name "Manufacturer Part") "AR03BTCX5003N") (field (name "Manufacturer") "Viking(光颉)"))
      (libsource (lib "easyedapro") (part "AR03BTCX5003N"))
    )
    (comp (ref "R37")
      (value "2MΩ")
      (footprint "easyedapro:R0603")
      (description "电阻类型:厚膜电阻;阻值:2MΩ;精度:±1%;功率:100mW;")
      (fields
        (field (name "Manufacturer Part") "0603WAF2004T5E")
        (field (name "Manufacturer") "UNI-ROYAL(厚声)")
      )
      (libsource (lib "easyedapro") (part "0603WAF2004T5E"))
    )
    (comp (ref "R38")
      (value "4.7kΩ")
      (footprint "easyedapro:R0603")
      (description "电阻类型:厚膜电阻;阻值:4.7kΩ;精度:±1%;功率:100mW;")
      (fields
        (field (name "Manufacturer Part") "0603WAF4701T5E")
        (field (name "Manufacturer") "UNI-ROYAL(厚声)")
      )
      (libsource (lib "easyedapro") (part "0603WAF4701T5E"))
    )
    (comp (ref "R39")
      (value "100Ω")
      (footprint "easyedapro:R0603")
      (description "电阻类型:厚膜电阻;阻值:100Ω;精度:±1%;功率:100mW;")
      (fields
        (field (name "Manufacturer Part") "0603WAF1000T5E")
        (field (name "Manufacturer") "UNI-ROYAL(厚声)")
      )
      (libsource (lib "easyedapro") (part "0603WAF1000T5E"))
    )
    (comp (ref "R40")
      (value "1kΩ")
      (footprint "easyedapro:R0603")
      (description "电阻类型:厚膜电阻;阻值:1kΩ;精度:±1%;功率:100mW;温度系数:±100ppm/°C;最大工作电压:75V;工作温度范围:-55°C~+155°C;")
      (fields
        (field (name "Manufacturer Part") "0603WAF1001T5E")
        (field (name "Manufacturer") "UNI-ROYAL(厚声)")
      )
      (libsource (lib "easyedapro") (part "0603WAF1001T5E"))
    )
    (comp (ref "R41") (value "10K") (footprint "easyedapro:R0603") (libsource (lib "easyedapro") (part "电阻")))
    (comp (ref "R42")
      (value "100kΩ")
      (footprint "easyedapro:R0603")
      (description "电阻类型:厚膜电阻;阻值:100kΩ;精度:±1%;功率:100mW;")
      (fields
        (field (name "Manufacturer Part") "0603WAF1003T5E")
        (field (name "Manufacturer") "UNI-ROYAL(厚声)")
      )
      (libsource (lib "easyedapro") (part "0603WAF1003T5E"))
    )
    (comp (ref "R43")
      (value "4.7kΩ")
      (footprint "easyedapro:R0603")
      (description "电阻类型:厚膜电阻;阻值:4.7kΩ;精度:±1%;功率:100mW;")
      (fields
        (field (name "Manufacturer Part") "0603WAF4701T5E")
        (field (name "Manufacturer") "UNI-ROYAL(厚声)")
      )
      (libsource (lib "easyedapro") (part "0603WAF4701T5E"))
    )
    (comp (ref "TP5")
      (value "~")
      (footprint "easyedapro:Test-Point-0.5mm")
      (description "Test Point 测试点")
      (libsource (lib "easyedapro") (part "Test-Point"))
    )
    (comp (ref "TP6")
      (value "~")
      (footprint "easyedapro:Test-Point-0.5mm")
      (description "Test Point 测试点")
      (libsource (lib "easyedapro") (part "Test-Point"))
    )
    (comp (ref "TP7")
      (value "~")
      (footprint "easyedapro:Test-Point-0.5mm")
      (description "Test Point 测试点")
      (libsource (lib "easyedapro") (part "Test-Point"))
    )
    (comp (ref "TP8")
      (value "~")
      (footprint "easyedapro:Test-Point-0.5mm")
      (description "Test Point 测试点")
      (libsource (lib "easyedapro") (part "Test-Point"))
    )
    (comp (ref "TP9")
      (value "~")
      (footprint "easyedapro:Test-Point-0.5mm")
      (description "Test Point 测试点")
      (libsource (lib "easyedapro") (part "Test-Point"))
    )
    (comp (ref "TP10")
      (value "~")
      (footprint "easyedapro:Test-Point-0.5mm")
      (description "Test Point 测试点")
      (libsource (lib "easyedapro") (part "Test-Point"))
    )
    (comp (ref "TP11")
      (value "~")
      (footprint "easyedapro:Test-Point-0.5mm")
      (description "Test Point 测试点")
      (libsource (lib "easyedapro") (part "Test-Point"))
    )
    (comp (ref "TP12")
      (value "~")
      (footprint "easyedapro:Test-Point-0.5mm")
      (description "Test Point 测试点")
      (libsource (lib "easyedapro") (part "Test-Point"))
    )
    (comp (ref "TP13")
      (value "~")
      (footprint "easyedapro:Test-Point-0.5mm")
      (description "Test Point 测试点")
      (libsource (lib "easyedapro") (part "Test-Point"))
    )
    (comp (ref "TP14")
      (value "~")
      (footprint "easyedapro:Test-Point-0.5mm")
      (description "Test Point 测试点")
      (libsource (lib "easyedapro") (part "Test-Point"))
    )
    (comp (ref "U4")
      (value "RT9013-33GB")
      (footprint "easyedapro:SOT-23-5_L3.0-W1.7-P0.95-LS2.8-BL")
      (description "输出类型:固定;输出极性:正;最大输入电压:5.5V;输出电压:3.3V;输出电流:500mA;电源纹波抑制比(PSRR):50dB@(10kHz);")
      (fields (field (name "Manufacturer") "RICHTEK(立锜)"))
      (libsource (lib "easyedapro") (part "RT9013-33GB"))
    )
    (comp (ref "U5")
      (value "RT9013-33GB")
      (footprint "easyedapro:SOT-23-5_L3.0-W1.7-P0.95-LS2.8-BL")
      (description "输出类型:固定;输出极性:正;最大输入电压:5.5V;输出电压:3.3V;输出电流:500mA;电源纹波抑制比(PSRR):50dB@(10kHz);")
      (fields (field (name "Manufacturer") "RICHTEK(立锜)"))
      (libsource (lib "easyedapro") (part "RT9013-33GB"))
    )
    (comp (ref "U6")
      (value "RT9013-33GB")
      (footprint "easyedapro:SOT-23-5_L3.0-W1.7-P0.95-LS2.8-BL")
      (description "输出类型:固定;输出极性:正;最大输入电压:5.5V;输出电压:3.3V;输出电流:500mA;电源纹波抑制比(PSRR):50dB@(10kHz);")
      (fields (field (name "Manufacturer") "RICHTEK(立锜)"))
      (libsource (lib "easyedapro") (part "RT9013-33GB"))
    )
    (comp (ref "开关")
      (value "TS-1002S-04526C")
      (footprint "easyedapro:SW-SMD_4P-L6.0-W6.0-P4.50-LS9.0-2")
      (description "触点电流:50mA;额定电压(DC):12V;电路结构:单刀单掷;安装方式:立贴;带灯:-;机械寿命:-;")
      (fields (field (name "Manufacturer") "XUNPU(讯普)"))
      (libsource (lib "easyedapro") (part "TS-1002S-04526C"))
    )
    (comp (ref "C32")
      (value "10uF")
      (footprint "easyedapro:C0603")
      (description "容值:10uF;精度:±20%;额定电压:16V;材质(温度系数):X5R;")
      (fields
        (field (name "Manufacturer Part") "CL10A106MO8NQNC")
        (field (name "Manufacturer") "SAMSUNG(三星)")
      )
      (libsource (lib "easyedapro") (part "CL10A106MO8NQNC"))
    )
    (comp (ref "C33")
      (value "20pF")
      (footprint "easyedapro:C0603")
      (description "温度系数:NP0;电容体长:-;容值:20pF;电容体宽:-;电容体厚度:-;精度:±5%;额定电压:50V;")
      (fields
        (field (name "Manufacturer Part") "CC0603JRNPO9BN200")
        (field (name "Manufacturer") "YAGEO(国巨)")
      )
      (libsource (lib "easyedapro") (part "CC0603JRNPO9BN200"))
    )
    (comp (ref "C34")
      (value "100nF")
      (footprint "easyedapro:C0603")
      (description "容值:100nF;精度:±10%;额定电压:16V;材质(温度系数):X7R;")
      (fields
        (field (name "Manufacturer Part") "CL10B104KO8NNNC")
        (field (name "Manufacturer") "SAMSUNG(三星)")
      )
      (libsource (lib "easyedapro") (part "CL10B104KO8NNNC"))
    )
    (comp (ref "C35")
      (value "100nF")
      (footprint "easyedapro:C0603")
      (description "容值:100nF;精度:±10%;额定电压:16V;材质(温度系数):X7R;")
      (fields
        (field (name "Manufacturer Part") "CL10B104KO8NNNC")
        (field (name "Manufacturer") "SAMSUNG(三星)")
      )
      (libsource (lib "easyedapro") (part "CL10B104KO8NNNC"))
    )
    (comp (ref "C36")
      (value "20pF")
      (footprint "easyedapro:C0603")
      (description "温度系数:NP0;电容体长:-;容值:20pF;电容体宽:-;电容体厚度:-;精度:±5%;额定电压:50V;")
      (fields
        (field (name "Manufacturer Part") "CC0603JRNPO9BN200")
        (field (name "Manufacturer") "YAGEO(国巨)")
      )
      (libsource (lib "easyedapro") (part "CC0603JRNPO9BN200"))
    )
    (comp (ref "C37")
      (value "100nF")
      (footprint "easyedapro:C0603")
      (description "容值:100nF;精度:±10%;额定电压:16V;材质(温度系数):X7R;")
      (fields
        (field (name "Manufacturer Part") "CL10B104KO8NNNC")
        (field (name "Manufacturer") "SAMSUNG(三星)")
      )
      (libsource (lib "easyedapro") (part "CL10B104KO8NNNC"))
    )
    (comp (ref "C38")
      (value "100nF")
      (footprint "easyedapro:C0603")
      (description "容值:100nF;精度:±10%;额定电压:16V;材质(温度系数):X7R;")
      (fields
        (field (name "Manufacturer Part") "CL10B104KO8NNNC")
        (field (name "Manufacturer") "SAMSUNG(三星)")
      )
      (libsource (lib "easyedapro") (part "CL10B104KO8NNNC"))
    )
    (comp (ref "C39")
      (value "15pF")
      (footprint "easyedapro:C0603")
      (description "容值:15pF;精度:±5%;额定电压:50V;材质(温度系数):NP0;")
      (fields
        (field (name "Manufacturer Part") "CC0603JRNPO9BN150")
        (field (name "Manufacturer") "YAGEO(国巨)")
      )
      (libsource (lib "easyedapro") (part "CC0603JRNPO9BN150"))
    )
    (comp (ref "C40")
      (value "100nF")
      (footprint "easyedapro:C0603")
      (description "容值:100nF;精度:±10%;额定电压:16V;材质(温度系数):X7R;")
      (fields
        (field (name "Manufacturer Part") "CL10B104KO8NNNC")
        (field (name "Manufacturer") "SAMSUNG(三星)")
      )
      (libsource (lib "easyedapro") (part "CL10B104KO8NNNC"))
    )
    (comp (ref "C41")
      (value "20pF")
      (footprint "easyedapro:C0603")
      (description "温度系数:NP0;电容体长:-;容值:20pF;电容体宽:-;电容体厚度:-;精度:±5%;额定电压:50V;")
      (fields
        (field (name "Manufacturer Part") "CC0603JRNPO9BN200")
        (field (name "Manufacturer") "YAGEO(国巨)")
      )
      (libsource (lib "easyedapro") (part "CC0603JRNPO9BN200"))
    )
    (comp (ref "C42")
      (value "20pF")
      (footprint "easyedapro:C0603")
      (description "温度系数:NP0;电容体长:-;容值:20pF;电容体宽:-;电容体厚度:-;精度:±5%;额定电压:50V;")
      (fields
        (field (name "Manufacturer Part") "CC0603JRNPO9BN200")
        (field (name "Manufacturer") "YAGEO(国巨)")
      )
      (libsource (lib "easyedapro") (part "CC0603JRNPO9BN200"))
    )
    (comp (ref "C43")
      (value "15pF")
      (footprint "easyedapro:C0603")
      (description "容值:15pF;精度:±5%;额定电压:50V;材质(温度系数):NP0;")
      (fields
        (field (name "Manufacturer Part") "CC0603JRNPO9BN150")
        (field (name "Manufacturer") "YAGEO(国巨)")
      )
      (libsource (lib "easyedapro") (part "CC0603JRNPO9BN150"))
    )
    (comp (ref "C44")
      (value "100nF")
      (footprint "easyedapro:C0603")
      (description "容值:100nF;精度:±10%;额定电压:16V;材质(温度系数):X7R;")
      (fields
        (field (name "Manufacturer Part") "CL10B104KO8NNNC")
        (field (name "Manufacturer") "SAMSUNG(三星)")
      )
      (libsource (lib "easyedapro") (part "CL10B104KO8NNNC"))
    )
    (comp (ref "C45")
      (value "100nF")
      (footprint "easyedapro:C0603")
      (description "容值:100nF;精度:±10%;额定电压:16V;材质(温度系数):X7R;")
      (fields
        (field (name "Manufacturer Part") "CL10B104KO8NNNC")
        (field (name "Manufacturer") "SAMSUNG(三星)")
      )
      (libsource (lib "easyedapro") (part "CL10B104KO8NNNC"))
    )
    (comp (ref "C46")
      (value "100nF")
      (footprint "easyedapro:C0603")
      (description "容值:100nF;精度:±10%;额定电压:16V;材质(温度系数):X7R;")
      (fields
        (field (name "Manufacturer Part") "CL10B104KO8NNNC")
        (field (name "Manufacturer") "SAMSUNG(三星)")
      )
      (libsource (lib "easyedapro") (part "CL10B104KO8NNNC"))
    )
    (comp (ref "C47")
      (value "100nF")
      (footprint "easyedapro:C0603")
      (description "容值:100nF;精度:±10%;额定电压:16V;材质(温度系数):X7R;")
      (fields
        (field (name "Manufacturer Part") "CL10B104KO8NNNC")
        (field (name "Manufacturer") "SAMSUNG(三星)")
      )
      (libsource (lib "easyedapro") (part "CL10B104KO8NNNC"))
    )
    (comp (ref "C48")
      (value "100nF")
      (footprint "easyedapro:C0603")
      (description "容值:100nF;精度:±10%;额定电压:16V;材质(温度系数):X7R;")
      (fields
        (field (name "Manufacturer Part") "CL10B104KO8NNNC")
        (field (name "Manufacturer") "SAMSUNG(三星)")
      )
      (libsource (lib "easyedapro") (part "CL10B104KO8NNNC"))
    )
    (comp (ref "C49")
      (value "100nF")
      (footprint "easyedapro:C0603")
      (description "容值:100nF;精度:±10%;额定电压:16V;材质(温度系数):X7R;")
      (fields
        (field (name "Manufacturer Part") "CL10B104KO8NNNC")
        (field (name "Manufacturer") "SAMSUNG(三星)")
      )
      (libsource (lib "easyedapro") (part "CL10B104KO8NNNC"))
    )
    (comp (ref "C50")
      (value "100nF")
      (footprint "easyedapro:C0603")
      (description "容值:100nF;精度:±10%;额定电压:16V;材质(温度系数):X7R;")
      (fields
        (field (name "Manufacturer Part") "CL10B104KO8NNNC")
        (field (name "Manufacturer") "SAMSUNG(三星)")
      )
      (libsource (lib "easyedapro") (part "CL10B104KO8NNNC"))
    )
    (comp (ref "C51")
      (value "10uF")
      (footprint "easyedapro:C0603")
      (description "容值:10uF;精度:±20%;额定电压:16V;材质(温度系数):X5R;")
      (fields
        (field (name "Manufacturer Part") "CL10A106MO8NQNC")
        (field (name "Manufacturer") "SAMSUNG(三星)")
      )
      (libsource (lib "easyedapro") (part "CL10A106MO8NQNC"))
    )
    (comp (ref "C52")
      (value "100nF")
      (footprint "easyedapro:C0603")
      (description "容值:100nF;精度:±10%;额定电压:16V;材质(温度系数):X7R;")
      (fields
        (field (name "Manufacturer Part") "CL10B104KO8NNNC")
        (field (name "Manufacturer") "SAMSUNG(三星)")
      )
      (libsource (lib "easyedapro") (part "CL10B104KO8NNNC"))
    )
    (comp (ref "C53")
      (value "10uF")
      (footprint "easyedapro:C0603")
      (description "容值:10uF;精度:±20%;额定电压:16V;材质(温度系数):X5R;")
      (fields
        (field (name "Manufacturer Part") "CL10A106MO8NQNC")
        (field (name "Manufacturer") "SAMSUNG(三星)")
      )
      (libsource (lib "easyedapro") (part "CL10A106MO8NQNC"))
    )
    (comp (ref "C54")
      (value "100nF")
      (footprint "easyedapro:C0603")
      (description "容值:100nF;精度:±10%;额定电压:16V;材质(温度系数):X7R;")
      (fields
        (field (name "Manufacturer Part") "CL10B104KO8NNNC")
        (field (name "Manufacturer") "SAMSUNG(三星)")
      )
      (libsource (lib "easyedapro") (part "CL10B104KO8NNNC"))
    )
    (comp (ref "C55")
      (value "100nF")
      (footprint "easyedapro:C0603")
      (description "容值:100nF;精度:±10%;额定电压:16V;材质(温度系数):X7R;")
      (fields
        (field (name "Manufacturer Part") "CL10B104KO8NNNC")
        (field (name "Manufacturer") "SAMSUNG(三星)")
      )
      (libsource (lib "easyedapro") (part "CL10B104KO8NNNC"))
    )
    (comp (ref "C56")
      (value "100nF")
      (footprint "easyedapro:C0603")
      (description "容值:100nF;精度:±10%;额定电压:16V;材质(温度系数):X7R;")
      (fields
        (field (name "Manufacturer Part") "CL10B104KO8NNNC")
        (field (name "Manufacturer") "SAMSUNG(三星)")
      )
      (libsource (lib "easyedapro") (part "CL10B104KO8NNNC"))
    )
    (comp (ref "C57")
      (value "1uF")
      (footprint "easyedapro:C0603")
      (description "容值:1uF;精度:±10%;额定电压:50V;材质(温度系数):X5R;")
      (fields
        (field (name "Manufacturer Part") "CL10A105KB8NNNC")
        (field (name "Manufacturer") "SAMSUNG(三星)")
      )
      (libsource (lib "easyedapro") (part "CL10A105KB8NNNC"))
    )
    (comp (ref "C58")
      (value "1uF")
      (footprint "easyedapro:C0603")
      (description "容值:1uF;精度:±10%;额定电压:50V;材质(温度系数):X5R;")
      (fields
        (field (name "Manufacturer Part") "CL10A105KB8NNNC")
        (field (name "Manufacturer") "SAMSUNG(三星)")
      )
      (libsource (lib "easyedapro") (part "CL10A105KB8NNNC"))
    )
    (comp (ref "D6")
      (value "1N4148W")
      (footprint "easyedapro:SOD-123_L2.8-W1.8-LS3.7-RD")
      (fields (field (name "Manufacturer") "CJ(江苏长电/长晶)"))
      (libsource (lib "easyedapro") (part "1N4148W T4"))
    )
    (comp (ref "D7")
      (value "SMAJ3.3A")
      (footprint "easyedapro:SMA_L4.3-W2.7-LS5.1-RD")
      (description "极性:单向;反向截止电压(Vrwm):3.3V;击穿电压:4.2V;反向漏电流(Ir):200uA;峰值脉冲电流(Ipp)@10/1000μs:25A;最大钳位电压:8.3V;")
      (fields (field (name "Manufacturer") "ZHIDE(志得)"))
      (libsource (lib "easyedapro") (part "SMAJ3.3A_C2917853"))
    )
    (comp (ref "D8")
      (value "SMAJ3.3A")
      (footprint "easyedapro:SMA_L4.3-W2.7-LS5.1-RD")
      (description "极性:单向;反向截止电压(Vrwm):3.3V;击穿电压:4.2V;反向漏电流(Ir):200uA;峰值脉冲电流(Ipp)@10/1000μs:25A;最大钳位电压:8.3V;")
      (fields (field (name "Manufacturer") "ZHIDE(志得)"))
      (libsource (lib "easyedapro") (part "SMAJ3.3A_C2917853"))
    )
    (comp (ref "D9")
      (value "SMAJ3.3A")
      (footprint "easyedapro:SMA_L4.3-W2.7-LS5.1-RD")
      (description "极性:单向;反向截止电压(Vrwm):3.3V;击穿电压:4.2V;反向漏电流(Ir):200uA;峰值脉冲电流(Ipp)@10/1000μs:25A;最大钳位电压:8.3V;")
      (fields (field (name "Manufacturer") "ZHIDE(志得)"))
      (libsource (lib "easyedapro") (part "SMAJ3.3A_C2917853"))
    )
    (comp (ref "D10")
      (value "SMAJ3.3A")
      (footprint "easyedapro:SMA_L4.3-W2.7-LS5.1-RD")
      (description "极性:单向;反向截止电压(Vrwm):3.3V;击穿电压:4.2V;反向漏电流(Ir):200uA;峰值脉冲电流(Ipp)@10/1000μs:25A;最大钳位电压:8.3V;")
      (fields (field (name "Manufacturer") "ZHIDE(志得)"))
      (libsource (lib "easyedapro") (part "SMAJ3.3A_C2917853"))
    )
    (comp (ref "E1")
      (value "CESDBLC5V0D3")
      (footprint "easyedapro:SOD-323_L1.8-W1.3-LS2.5-BI")
      (description "极性:双向;反向截止电压(Vrwm):5V;击穿电压(VBR):5.8V;峰值脉冲电流(Ipp)@8/20us:5A;钳位电压(Vc)@Ipp:10V;")
      (fields (field (name "Manufacturer") "CJ(江苏长电/长晶)"))
      (libsource (lib "easyedapro") (part "CESDBLC5V0D3"))
    )
    (comp (ref "E2")
      (value "CESDBLC5V0D3")
      (footprint "easyedapro:SOD-323_L1.8-W1.3-LS2.5-BI")
      (description "极性:双向;反向截止电压(Vrwm):5V;击穿电压(VBR):5.8V;峰值脉冲电流(Ipp)@8/20us:5A;钳位电压(Vc)@Ipp:10V;")
      (fields (field (name "Manufacturer") "CJ(江苏长电/长晶)"))
      (libsource (lib "easyedapro") (part "CESDBLC5V0D3"))
    )
    (comp (ref "E3")
      (value "CESDBLC5V0D3")
      (footprint "easyedapro:SOD-323_L1.8-W1.3-LS2.5-BI")
      (description "极性:双向;反向截止电压(Vrwm):5V;击穿电压(VBR):5.8V;峰值脉冲电流(Ipp)@8/20us:5A;钳位电压(Vc)@Ipp:10V;")
      (fields (field (name "Manufacturer") "CJ(江苏长电/长晶)"))
      (libsource (lib "easyedapro") (part "CESDBLC5V0D3"))
    )
    (comp (ref "E4")
      (value "CESDBLC5V0D3")
      (footprint "easyedapro:SOD-323_L1.8-W1.3-LS2.5-BI")
      (description "极性:双向;反向截止电压(Vrwm):5V;击穿电压(VBR):5.8V;峰值脉冲电流(Ipp)@8/20us:5A;钳位电压(Vc)@Ipp:10V;")
      (fields (field (name "Manufacturer") "CJ(江苏长电/长晶)"))
      (libsource (lib "easyedapro") (part "CESDBLC5V0D3"))
    )
    (comp (ref "E5")
      (value "CESDBLC5V0D3")
      (footprint "easyedapro:SOD-323_L1.8-W1.3-LS2.5-BI")
      (description "极性:双向;反向截止电压(Vrwm):5V;击穿电压(VBR):5.8V;峰值脉冲电流(Ipp)@8/20us:5A;钳位电压(Vc)@Ipp:10V;")
      (fields (field (name "Manufacturer") "CJ(江苏长电/长晶)"))
      (libsource (lib "easyedapro") (part "CESDBLC5V0D3"))
    )
    (comp (ref "E6")
      (value "CESDBLC5V0D3")
      (footprint "easyedapro:SOD-323_L1.8-W1.3-LS2.5-BI")
      (description "极性:双向;反向截止电压(Vrwm):5V;击穿电压(VBR):5.8V;峰值脉冲电流(Ipp)@8/20us:5A;钳位电压(Vc)@Ipp:10V;")
      (fields (field (name "Manufacturer") "CJ(江苏长电/长晶)"))
      (libsource (lib "easyedapro") (part "CESDBLC5V0D3"))
    )
    (comp (ref "E7")
      (value "CESDBLC5V0D3")
      (footprint "easyedapro:SOD-323_L1.8-W1.3-LS2.5-BI")
      (description "极性:双向;反向截止电压(Vrwm):5V;击穿电压(VBR):5.8V;峰值脉冲电流(Ipp)@8/20us:5A;钳位电压(Vc)@Ipp:10V;")
      (fields (field (name "Manufacturer") "CJ(江苏长电/长晶)"))
      (libsource (lib "easyedapro") (part "CESDBLC5V0D3"))
    )
    (comp (ref "E8")
      (value "CESDBLC5V0D3")
      (footprint "easyedapro:SOD-323_L1.8-W1.3-LS2.5-BI")
      (description "极性:双向;反向截止电压(Vrwm):5V;击穿电压(VBR):5.8V;峰值脉冲电流(Ipp)@8/20us:5A;钳位电压(Vc)@Ipp:10V;")
      (fields (field (name "Manufacturer") "CJ(江苏长电/长晶)"))
      (libsource (lib "easyedapro") (part "CESDBLC5V0D3"))
    )
    (comp (ref "E9")
      (value "CESDBLC5V0D3")
      (footprint "easyedapro:SOD-323_L1.8-W1.3-LS2.5-BI")
      (description "极性:双向;反向截止电压(Vrwm):5V;击穿电压(VBR):5.8V;峰值脉冲电流(Ipp)@8/20us:5A;钳位电压(Vc)@Ipp:10V;")
      (fields (field (name "Manufacturer") "CJ(江苏长电/长晶)"))
      (libsource (lib "easyedapro") (part "CESDBLC5V0D3"))
    )
    (comp (ref "E10")
      (value "CESDBLC5V0D3")
      (footprint "easyedapro:SOD-323_L1.8-W1.3-LS2.5-BI")
      (description "极性:双向;反向截止电压(Vrwm):5V;击穿电压(VBR):5.8V;峰值脉冲电流(Ipp)@8/20us:5A;钳位电压(Vc)@Ipp:10V;")
      (fields (field (name "Manufacturer") "CJ(江苏长电/长晶)"))
      (libsource (lib "easyedapro") (part "CESDBLC5V0D3"))
    )
    (comp (ref "H4")
      (value "2.54-1*4P反弯排针")
      (footprint "easyedapro:HDR-TH_4P-P2.54-H-M-W10.4")
      (fields (field (name "Manufacturer") "BOOMELE(博穆精密)"))
      (libsource (lib "easyedapro") (part "2.54-1*4P反弯排针"))
    )
    (comp (ref "I1")
      (value "2.54-1*8P母环保")
      (footprint "easyedapro:HDR-TH_8P-P2.54-V-F-1")
      (description "排数:单排;总孔位数:8;间距:2.54mm;插孔结构:1x8P;行距:-;安装类型:直插;塑高:-;触头材质:-;触头镀层:-;")
      (fields (field (name "Manufacturer") "BOOMELE(博穆精密)"))
      (libsource (lib "easyedapro") (part "Header-Female-2.54_1x8"))
    )
    (comp (ref "K1")
      (value "GT-TC060A-H025-L1")
      (footprint "easyedapro:SW-SMD_L6.1-W3.5-LS8.0")
      (description "开关长度:6.05mm;开关宽度:3.5mm;开关高度:2.5mm;")
      (fields (field (name "Manufacturer") "G-Switch(品赞)"))
      (libsource (lib "easyedapro") (part "GT-TC060A-H025-L1"))
    )
    (comp (ref "K2")
      (value "GT-TC060A-H025-L1")
      (footprint "easyedapro:SW-SMD_L6.1-W3.5-LS8.0")
      (description "开关长度:6.05mm;开关宽度:3.5mm;开关高度:2.5mm;")
      (fields (field (name "Manufacturer") "G-Switch(品赞)"))
      (libsource (lib "easyedapro") (part "GT-TC060A-H025-L1"))
    )
    (comp (ref "K3")
      (value "GT-TC060A-H025-L1")
      (footprint "easyedapro:SW-SMD_L6.1-W3.5-LS8.0")
      (description "开关长度:6.05mm;开关宽度:3.5mm;开关高度:2.5mm;")
      (fields (field (name "Manufacturer") "G-Switch(品赞)"))
      (libsource (lib "easyedapro") (part "GT-TC060A-H025-L1"))
    )
    (comp (ref "K4")
      (value "GT-TC060A-H025-L1")
      (footprint "easyedapro:SW-SMD_L6.1-W3.5-LS8.0")
      (description "开关长度:6.05mm;开关宽度:3.5mm;开关高度:2.5mm;")
      (fields (field (name "Manufacturer") "G-Switch(品赞)"))
      (libsource (lib "easyedapro") (part "GT-TC060A-H025-L1"))
    )
    (comp (ref "K5")
      (value "GT-TC060A-H025-L1")
      (footprint "easyedapro:SW-SMD_L6.1-W3.5-LS8.0")
      (description "开关长度:6.05mm;开关宽度:3.5mm;开关高度:2.5mm;")
      (fields (field (name "Manufacturer") "G-Switch(品赞)"))
      (libsource (lib "easyedapro") (part "GT-TC060A-H025-L1"))
    )
    (comp (ref "K6")
      (value "GT-TC060A-H025-L1")
      (footprint "easyedapro:SW-SMD_L6.1-W3.5-LS8.0")
      (description "开关长度:6.05mm;开关宽度:3.5mm;开关高度:2.5mm;")
      (fields (field (name "Manufacturer") "G-Switch(品赞)"))
      (libsource (lib "easyedapro") (part "GT-TC060A-H025-L1"))
    )
    (comp (ref "Krest")
      (value "TS-1101-C-W")
      (fields (field (name "Manufacturer") "XKB Connectivity(中国星坤)"))
      (libsource (lib "easyedapro") (part "TS-1101-C-W"))
    )
    (comp (ref "LED6")
      (value "XL-2012RGBC")
      (footprint "easyedapro:LED-SMD_4P-L2.0-W1.3-BR")
      (description "发光颜色:RGB三色;二极管配置:-;主波长:619nm~624nm；463nm~466nm；524nm~527nm;色温:-;功率:80mW；80mW；55mW;安装方式:正贴;")
      (fields (field (name "Manufacturer") "XINGLIGHT(成兴光)") (field (name "Emitted Color") "RGB"))
      (libsource (lib "easyedapro") (part "XL-2012RGBC"))
    )
    (comp (ref "LED7")
      (value "NCD0805G1")
      (footprint "easyedapro:LED0805-R-RD")
      (description "翠绿")
      (fields (field (name "Manufacturer") "国星光电"))
      (libsource (lib "easyedapro") (part "FC-2012UGK-520D5"))
    )
    (comp (ref "LED8")
      (value "NCD0805G1")
      (footprint "easyedapro:LED0805-R-RD")
      (description "翠绿")
      (fields (field (name "Manufacturer") "国星光电"))
      (libsource (lib "easyedapro") (part "FC-2012UGK-520D5"))
    )
    (comp (ref "LED9")
      (value "NCD0805G1")
      (footprint "easyedapro:LED0805-R-RD")
      (description "翠绿")
      (fields (field (name "Manufacturer") "国星光电"))
      (libsource (lib "easyedapro") (part "FC-2012UGK-520D5"))
    )
    (comp (ref "LED10")
      (value "NCD0805G1")
      (footprint "easyedapro:LED0805-R-RD")
      (description "翠绿")
      (fields (field (name "Manufacturer") "国星光电"))
      (libsource (lib "easyedapro") (part "FC-2012UGK-520D5"))
    )
    (comp (ref "MCU1")
      (value "STM32F103RCT6")
      (footprint "easyedapro:LQFP-64_L10.0-W10.0-P0.50-LS12.0-BL")
      (fields (field (name "Manufacturer") "ST(意法半导体)"))
      (libsource (lib "easyedapro") (part "STM32F103RCT6"))
    )
    (comp (ref "Q8")
      (value "S8550")
      (footprint "easyedapro:SOT-23-3_L2.9-W1.4-P1.90-LS2.6-BR")
      (fields (field (name "Manufacturer") "WPMtek(维攀微)"))
      (libsource (lib "easyedapro") (part "S8550_C2688230"))
    )
    (comp (ref "Q9")
      (value "AO3401A")
      (footprint "easyedapro:SOT-23-3_L2.9-W1.3-P1.90-LS2.4-BR")
      (fields (field (name "Manufacturer") "HUASHUO(华朔)"))
      (libsource (lib "easyedapro") (part "AO3401A_C700954"))
    )
    (comp (ref "Q10")
      (value "AO3400A")
      (footprint "easyedapro:SOT-23-3_L2.9-W1.3-P1.90-LS2.4-BR")
      (fields (field (name "Manufacturer") "HUASHUO(华朔)"))
      (libsource (lib "easyedapro") (part "AO3400A_C700953"))
    )
    (comp (ref "R44")
      (value "10kΩ")
      (footprint "easyedapro:R0603")
      (description "电阻类型:厚膜电阻;阻值:10kΩ;精度:±1%;功率:100mW;温度系数:±100ppm/℃;最大工作电压:75V;工作温度范围:-55℃~+155℃;")
      (fields
        (field (name "Manufacturer Part") "0603WAF1002T5E")
        (field (name "Manufacturer") "UNI-ROYAL(厚声)")
      )
      (libsource (lib "easyedapro") (part "0603WAF1002T5E"))
    )
    (comp (ref "R45")
      (value "1kΩ")
      (footprint "easyedapro:R0603")
      (description "电阻类型:厚膜电阻;阻值:1kΩ;精度:±1%;功率:100mW;温度系数:±100ppm/℃;最大工作电压:75V;工作温度范围:-55℃~+155℃;")
      (fields
        (field (name "Manufacturer Part") "0603WAF1001T5E")
        (field (name "Manufacturer") "UNI-ROYAL(厚声)")
      )
      (libsource (lib "easyedapro") (part "0603WAF1001T5E"))
    )
    (comp (ref "R46")
      (value "10kΩ")
      (footprint "easyedapro:R0603")
      (description "电阻类型:厚膜电阻;阻值:10kΩ;精度:±1%;功率:100mW;温度系数:±100ppm/℃;最大工作电压:75V;工作温度范围:-55℃~+155℃;")
      (fields
        (field (name "Manufacturer Part") "0603WAF1002T5E")
        (field (name "Manufacturer") "UNI-ROYAL(厚声)")
      )
      (libsource (lib "easyedapro") (part "0603WAF1002T5E"))
    )
    (comp (ref "R47")
      (value "1kΩ")
      (footprint "easyedapro:R0603")
      (description "电阻类型:厚膜电阻;阻值:1kΩ;精度:±1%;功率:100mW;温度系数:±100ppm/℃;最大工作电压:75V;工作温度范围:-55℃~+155℃;")
      (fields
        (field (name "Manufacturer Part") "0603WAF1001T5E")
        (field (name "Manufacturer") "UNI-ROYAL(厚声)")
      )
      (libsource (lib "easyedapro") (part "0603WAF1001T5E"))
    )
    (comp (ref "R48")
      (value "1kΩ")
      (footprint "easyedapro:R0603")
      (description "电阻类型:厚膜电阻;阻值:1kΩ;精度:±1%;功率:100mW;温度系数:±100ppm/℃;最大工作电压:75V;工作温度范围:-55℃~+155℃;")
      (fields
        (field (name "Manufacturer Part") "0603WAF1001T5E")
        (field (name "Manufacturer") "UNI-ROYAL(厚声)")
      )
      (libsource (lib "easyedapro") (part "0603WAF1001T5E"))
    )
    (comp (ref "R49")
      (value "10kΩ")
      (footprint "easyedapro:R0603")
      (description "电阻类型:厚膜电阻;阻值:10kΩ;精度:±1%;功率:100mW;温度系数:±100ppm/℃;最大工作电压:75V;工作温度范围:-55℃~+155℃;")
      (fields
        (field (name "Manufacturer Part") "0603WAF1002T5E")
        (field (name "Manufacturer") "UNI-ROYAL(厚声)")
      )
      (libsource (lib "easyedapro") (part "0603WAF1002T5E"))
    )
    (comp (ref "R50")
      (value "22Ω")
      (footprint "easyedapro:R0603")
      (description "电阻类型:厚膜电阻;阻值:22Ω;精度:±1%;功率:100mW;温度系数:±100ppm/℃;最大工作电压:75V;工作温度范围:-55℃~+155℃;")
      (fields
        (field (name "Manufacturer Part") "0603WAF220JT5E")
        (field (name "Manufacturer") "UNI-ROYAL(厚声)")
      )
      (libsource (lib "easyedapro") (part "0603WAF220JT5E"))
    )
    (comp (ref "R51")
      (value "22Ω")
      (footprint "easyedapro:R0603")
      (description "电阻类型:厚膜电阻;阻值:22Ω;精度:±1%;功率:100mW;温度系数:±100ppm/℃;最大工作电压:75V;工作温度范围:-55℃~+155℃;")
      (fields
        (field (name "Manufacturer Part") "0603WAF220JT5E")
        (field (name "Manufacturer") "UNI-ROYAL(厚声)")
      )
      (libsource (lib "easyedapro") (part "0603WAF220JT5E"))
    )
    (comp (ref "R52")
      (value "22Ω")
      (footprint "easyedapro:R0603")
      (description "电阻类型:厚膜电阻;阻值:22Ω;精度:±1%;功率:100mW;温度系数:±100ppm/℃;最大工作电压:75V;工作温度范围:-55℃~+155℃;")
      (fields
        (field (name "Manufacturer Part") "0603WAF220JT5E")
        (field (name "Manufacturer") "UNI-ROYAL(厚声)")
      )
      (libsource (lib "easyedapro") (part "0603WAF220JT5E"))
    )
    (comp (ref "R53")
      (value "22Ω")
      (footprint "easyedapro:R0603")
      (description "电阻类型:厚膜电阻;阻值:22Ω;精度:±1%;功率:100mW;温度系数:±100ppm/℃;最大工作电压:75V;工作温度范围:-55℃~+155℃;")
      (fields
        (field (name "Manufacturer Part") "0603WAF220JT5E")
        (field (name "Manufacturer") "UNI-ROYAL(厚声)")
      )
      (libsource (lib "easyedapro") (part "0603WAF220JT5E"))
    )
    (comp (ref "R54")
      (value "22Ω")
      (footprint "easyedapro:R0603")
      (description "电阻类型:厚膜电阻;阻值:22Ω;精度:±1%;功率:100mW;温度系数:±100ppm/℃;最大工作电压:75V;工作温度范围:-55℃~+155℃;")
      (fields
        (field (name "Manufacturer Part") "0603WAF220JT5E")
        (field (name "Manufacturer") "UNI-ROYAL(厚声)")
      )
      (libsource (lib "easyedapro") (part "0603WAF220JT5E"))
    )
    (comp (ref "R55")
      (value "22Ω")
      (footprint "easyedapro:R0603")
      (description "电阻类型:厚膜电阻;阻值:22Ω;精度:±1%;功率:100mW;温度系数:±100ppm/℃;最大工作电压:75V;工作温度范围:-55℃~+155℃;")
      (fields
        (field (name "Manufacturer Part") "0603WAF220JT5E")
        (field (name "Manufacturer") "UNI-ROYAL(厚声)")
      )
      (libsource (lib "easyedapro") (part "0603WAF220JT5E"))
    )
    (comp (ref "R56")
      (value "3.3kΩ")
      (footprint "easyedapro:R0603")
      (description "电阻类型:厚膜电阻;阻值:3.3kΩ;精度:±1%;功率:100mW;温度系数:±100ppm/°C;")
      (fields
        (field (name "Manufacturer Part") "0603WAF3301T5E")
        (field (name "Manufacturer") "UNI-ROYAL(厚声)")
      )
      (libsource (lib "easyedapro") (part "0603WAF3301T5E"))
    )
    (comp (ref "R57")
      (value "3.3kΩ")
      (footprint "easyedapro:R0603")
      (description "电阻类型:厚膜电阻;阻值:3.3kΩ;精度:±1%;功率:100mW;温度系数:±100ppm/°C;")
      (fields
        (field (name "Manufacturer Part") "0603WAF3301T5E")
        (field (name "Manufacturer") "UNI-ROYAL(厚声)")
      )
      (libsource (lib "easyedapro") (part "0603WAF3301T5E"))
    )
    (comp (ref "R58")
      (value "3.3kΩ")
      (footprint "easyedapro:R0603")
      (description "电阻类型:厚膜电阻;阻值:3.3kΩ;精度:±1%;功率:100mW;温度系数:±100ppm/°C;")
      (fields
        (field (name "Manufacturer Part") "0603WAF3301T5E")
        (field (name "Manufacturer") "UNI-ROYAL(厚声)")
      )
      (libsource (lib "easyedapro") (part "0603WAF3301T5E"))
    )
    (comp (ref "R59")
      (value "3.3kΩ")
      (footprint "easyedapro:R0603")
      (description "电阻类型:厚膜电阻;阻值:3.3kΩ;精度:±1%;功率:100mW;温度系数:±100ppm/°C;")
      (fields
        (field (name "Manufacturer Part") "0603WAF3301T5E")
        (field (name "Manufacturer") "UNI-ROYAL(厚声)")
      )
      (libsource (lib "easyedapro") (part "0603WAF3301T5E"))
    )
    (comp (ref "R60")
      (value "3.3kΩ")
      (footprint "easyedapro:R0603")
      (description "电阻类型:厚膜电阻;阻值:3.3kΩ;精度:±1%;功率:100mW;温度系数:±100ppm/°C;")
      (fields
        (field (name "Manufacturer Part") "0603WAF3301T5E")
        (field (name "Manufacturer") "UNI-ROYAL(厚声)")
      )
      (libsource (lib "easyedapro") (part "0603WAF3301T5E"))
    )
    (comp (ref "R61")
      (value "3.3kΩ")
      (footprint "easyedapro:R0603")
      (description "电阻类型:厚膜电阻;阻值:3.3kΩ;精度:±1%;功率:100mW;温度系数:±100ppm/°C;")
      (fields
        (field (name "Manufacturer Part") "0603WAF3301T5E")
        (field (name "Manufacturer") "UNI-ROYAL(厚声)")
      )
      (libsource (lib "easyedapro") (part "0603WAF3301T5E"))
    )
    (comp (ref "R62")
      (value "3.3kΩ")
      (footprint "easyedapro:R0603")
      (description "电阻类型:厚膜电阻;阻值:3.3kΩ;精度:±1%;功率:100mW;温度系数:±100ppm/°C;")
      (fields
        (field (name "Manufacturer Part") "0603WAF3301T5E")
        (field (name "Manufacturer") "UNI-ROYAL(厚声)")
      )
      (libsource (lib "easyedapro") (part "0603WAF3301T5E"))
    )
    (comp (ref "R63")
      (value "4.7kΩ")
      (footprint "easyedapro:R0603")
      (description "阻值:4.7kΩ;精度:±1%;功率:100mW;温度系数:±100ppm/℃;最大工作电压:75V;工作温度范围:-55℃~+155℃;")
      (fields (field (name "Manufacturer Part") "RC0603FR-074K7L") (field (name "Manufacturer") "YAGEO(国巨)"))
      (libsource (lib "easyedapro") (part "RC0603FR-074K7L"))
    )
    (comp (ref "R64")
      (value "4.7kΩ")
      (footprint "easyedapro:R0603")
      (description "阻值:4.7kΩ;精度:±1%;功率:100mW;温度系数:±100ppm/℃;最大工作电压:75V;工作温度范围:-55℃~+155℃;")
      (fields (field (name "Manufacturer Part") "RC0603FR-074K7L") (field (name "Manufacturer") "YAGEO(国巨)"))
      (libsource (lib "easyedapro") (part "RC0603FR-074K7L"))
    )
    (comp (ref "R65")
      (value "4.7kΩ")
      (footprint "easyedapro:R0603")
      (description "阻值:4.7kΩ;精度:±1%;功率:100mW;温度系数:±100ppm/℃;最大工作电压:75V;工作温度范围:-55℃~+155℃;")
      (fields (field (name "Manufacturer Part") "RC0603FR-074K7L") (field (name "Manufacturer") "YAGEO(国巨)"))
      (libsource (lib "easyedapro") (part "RC0603FR-074K7L"))
    )
    (comp (ref "R66")
      (value "4.7kΩ")
      (footprint "easyedapro:R0603")
      (description "阻值:4.7kΩ;精度:±1%;功率:100mW;温度系数:±100ppm/℃;最大工作电压:75V;工作温度范围:-55℃~+155℃;")
      (fields (field (name "Manufacturer Part") "RC0603FR-074K7L") (field (name "Manufacturer") "YAGEO(国巨)"))
      (libsource (lib "easyedapro") (part "RC0603FR-074K7L"))
    )
    (comp (ref "R67")
      (value "4.7kΩ")
      (footprint "easyedapro:R0603")
      (description "阻值:4.7kΩ;精度:±1%;功率:100mW;温度系数:±100ppm/℃;最大工作电压:75V;工作温度范围:-55℃~+155℃;")
      (fields (field (name "Manufacturer Part") "RC0603FR-074K7L") (field (name "Manufacturer") "YAGEO(国巨)"))
      (libsource (lib "easyedapro") (part "RC0603FR-074K7L"))
    )
    (comp (ref "R68")
      (value "4.7kΩ")
      (footprint "easyedapro:R0603")
      (description "阻值:4.7kΩ;精度:±1%;功率:100mW;温度系数:±100ppm/℃;最大工作电压:75V;工作温度范围:-55℃~+155℃;")
      (fields (field (name "Manufacturer Part") "RC0603FR-074K7L") (field (name "Manufacturer") "YAGEO(国巨)"))
      (libsource (lib "easyedapro") (part "RC0603FR-074K7L"))
    )
    (comp (ref "R69")
      (value "22Ω")
      (footprint "easyedapro:R0603")
      (description "电阻类型:厚膜电阻;阻值:22Ω;精度:±1%;功率:100mW;温度系数:±100ppm/℃;最大工作电压:75V;工作温度范围:-55℃~+155℃;")
      (fields
        (field (name "Manufacturer Part") "0603WAF220JT5E")
        (field (name "Manufacturer") "UNI-ROYAL(厚声)")
      )
      (libsource (lib "easyedapro") (part "0603WAF220JT5E"))
    )
    (comp (ref "R70")
      (value "22Ω")
      (footprint "easyedapro:R0603")
      (description "电阻类型:厚膜电阻;阻值:22Ω;精度:±1%;功率:100mW;温度系数:±100ppm/℃;最大工作电压:75V;工作温度范围:-55℃~+155℃;")
      (fields
        (field (name "Manufacturer Part") "0603WAF220JT5E")
        (field (name "Manufacturer") "UNI-ROYAL(厚声)")
      )
      (libsource (lib "easyedapro") (part "0603WAF220JT5E"))
    )
    (comp (ref "R71")
      (value "22Ω")
      (footprint "easyedapro:R0603")
      (description "电阻类型:厚膜电阻;阻值:22Ω;精度:±1%;功率:100mW;温度系数:±100ppm/℃;最大工作电压:75V;工作温度范围:-55℃~+155℃;")
      (fields
        (field (name "Manufacturer Part") "0603WAF220JT5E")
        (field (name "Manufacturer") "UNI-ROYAL(厚声)")
      )
      (libsource (lib "easyedapro") (part "0603WAF220JT5E"))
    )
    (comp (ref "R72")
      (value "22Ω")
      (footprint "easyedapro:R0603")
      (description "电阻类型:厚膜电阻;阻值:22Ω;精度:±1%;功率:100mW;温度系数:±100ppm/℃;最大工作电压:75V;工作温度范围:-55℃~+155℃;")
      (fields
        (field (name "Manufacturer Part") "0603WAF220JT5E")
        (field (name "Manufacturer") "UNI-ROYAL(厚声)")
      )
      (libsource (lib "easyedapro") (part "0603WAF220JT5E"))
    )
    (comp (ref "R73")
      (value "10kΩ")
      (footprint "easyedapro:R0603")
      (description "电阻类型:厚膜电阻;阻值:10kΩ;精度:±1%;功率:100mW;温度系数:±100ppm/℃;最大工作电压:75V;工作温度范围:-55℃~+155℃;")
      (fields
        (field (name "Manufacturer Part") "0603WAF1002T5E")
        (field (name "Manufacturer") "UNI-ROYAL(厚声)")
      )
      (libsource (lib "easyedapro") (part "0603WAF1002T5E"))
    )
    (comp (ref "R74")
      (value "10kΩ")
      (footprint "easyedapro:R0603")
      (description "电阻类型:厚膜电阻;阻值:10kΩ;精度:±1%;功率:100mW;温度系数:±100ppm/℃;最大工作电压:75V;工作温度范围:-55℃~+155℃;")
      (fields
        (field (name "Manufacturer Part") "0603WAF1002T5E")
        (field (name "Manufacturer") "UNI-ROYAL(厚声)")
      )
      (libsource (lib "easyedapro") (part "0603WAF1002T5E"))
    )
    (comp (ref "R75")
      (value "100kΩ")
      (footprint "easyedapro:R0603")
      (description "阻值:100kΩ;精度:±5%;功率:100mW;温度系数:±100ppm/°C;最大工作电压:50V;工作温度范围:-55°C~+155°C;")
      (fields (field (name "Manufacturer Part") "RS-03K104JT") (field (name "Manufacturer") "FH(风华)"))
      (libsource (lib "easyedapro") (part "RS-03K104JT"))
    )
    (comp (ref "R76")
      (value "10kΩ")
      (footprint "easyedapro:R0603")
      (description "电阻类型:厚膜电阻;阻值:10kΩ;精度:±1%;功率:100mW;温度系数:±100ppm/℃;最大工作电压:75V;工作温度范围:-55℃~+155℃;")
      (fields
        (field (name "Manufacturer Part") "0603WAF1002T5E")
        (field (name "Manufacturer") "UNI-ROYAL(厚声)")
      )
      (libsource (lib "easyedapro") (part "0603WAF1002T5E"))
    )
    (comp (ref "R77")
      (value "10kΩ")
      (footprint "easyedapro:R0603")
      (description "电阻类型:厚膜电阻;阻值:10kΩ;精度:±1%;功率:100mW;温度系数:±100ppm/℃;最大工作电压:75V;工作温度范围:-55℃~+155℃;")
      (fields
        (field (name "Manufacturer Part") "0603WAF1002T5E")
        (field (name "Manufacturer") "UNI-ROYAL(厚声)")
      )
      (libsource (lib "easyedapro") (part "0603WAF1002T5E"))
    )
    (comp (ref "R78")
      (value "0Ω")
      (footprint "easyedapro:R0603")
      (description "电阻类型:厚膜电阻;阻值:0Ω;精度:±1%;功率:100mW;")
      (fields
        (field (name "Manufacturer Part") "0603WAF0000T5E")
        (field (name "Manufacturer") "UNI-ROYAL(厚声)")
      )
      (libsource (lib "easyedapro") (part "0603WAF0000T5E"))
    )
    (comp (ref "R79")
      (value "100kΩ")
      (footprint "easyedapro:R0603")
      (description "阻值:100kΩ;精度:±5%;功率:100mW;温度系数:±100ppm/°C;最大工作电压:50V;工作温度范围:-55°C~+155°C;")
      (fields (field (name "Manufacturer Part") "RS-03K104JT") (field (name "Manufacturer") "FH(风华)"))
      (libsource (lib "easyedapro") (part "RS-03K104JT"))
    )
    (comp (ref "T1")
      (value "2.54-1*8P母环保")
      (footprint "easyedapro:HDR-TH_8P-P2.54-V-F-1")
      (description "排数:单排;总孔位数:8;间距:2.54mm;插孔结构:1x8P;行距:-;安装类型:直插;塑高:-;触头材质:-;触头镀层:-;")
      (fields (field (name "Manufacturer") "BOOMELE(博穆精密)"))
      (libsource (lib "easyedapro") (part "Header-Female-2.54_1x8"))
    )
    (comp (ref "TP15")
      (value "~")
      (footprint "easyedapro:Test-Point-0.5mm")
      (description "Test Point 测试点")
      (libsource (lib "easyedapro") (part "Test-Point"))
    )
    (comp (ref "TP16")
      (value "~")
      (footprint "easyedapro:Test-Point-0.5mm")
      (description "Test Point 测试点")
      (libsource (lib "easyedapro") (part "Test-Point"))
    )
    (comp (ref "TP17")
      (value "~")
      (footprint "easyedapro:Test-Point-0.5mm")
      (description "Test Point 测试点")
      (libsource (lib "easyedapro") (part "Test-Point"))
    )
    (comp (ref "TP18")
      (value "~")
      (footprint "easyedapro:Test-Point-0.5mm")
      (description "Test Point 测试点")
      (libsource (lib "easyedapro") (part "Test-Point"))
    )
    (comp (ref "TP19")
      (value "~")
      (footprint "easyedapro:Test-Point-0.5mm")
      (description "Test Point 测试点")
      (libsource (lib "easyedapro") (part "Test-Point"))
    )
    (comp (ref "TP20")
      (value "~")
      (footprint "easyedapro:Test-Point-0.5mm")
      (description "Test Point 测试点")
      (libsource (lib "easyedapro") (part "Test-Point"))
    )
    (comp (ref "TP21")
      (value "~")
      (footprint "easyedapro:Test-Point-0.5mm")
      (description "Test Point 测试点")
      (libsource (lib "easyedapro") (part "Test-Point"))
    )
    (comp (ref "TP22")
      (value "~")
      (footprint "easyedapro:Test-Point-0.5mm")
      (description "Test Point 测试点")
      (libsource (lib "easyedapro") (part "Test-Point"))
    )
    (comp (ref "TP23")
      (value "~")
      (footprint "easyedapro:Test-Point-0.5mm")
      (description "Test Point 测试点")
      (libsource (lib "easyedapro") (part "Test-Point"))
    )
    (comp (ref "TP24")
      (value "~")
      (footprint "easyedapro:Test-Point-0.5mm")
      (description "Test Point 测试点")
      (libsource (lib "easyedapro") (part "Test-Point"))
    )
    (comp (ref "TP25")
      (value "~")
      (footprint "easyedapro:Test-Point-0.5mm")
      (description "Test Point 测试点")
      (libsource (lib "easyedapro") (part "Test-Point"))
    )
    (comp (ref "TP26")
      (value "~")
      (footprint "easyedapro:螺丝孔")
      (description "内径3.0mm，外径4.5mm金属化螺丝孔")
      (libsource (lib "easyedapro") (part "螺丝孔"))
    )
    (comp (ref "TP27")
      (value "~")
      (footprint "easyedapro:螺丝孔")
      (description "内径3.0mm，外径4.5mm金属化螺丝孔")
      (libsource (lib "easyedapro") (part "螺丝孔"))
    )
    (comp (ref "TP28")
      (value "~")
      (footprint "easyedapro:螺丝孔")
      (description "内径3.0mm，外径4.5mm金属化螺丝孔")
      (libsource (lib "easyedapro") (part "螺丝孔"))
    )
    (comp (ref "TP29")
      (value "~")
      (footprint "easyedapro:螺丝孔")
      (description "内径3.0mm，外径4.5mm金属化螺丝孔")
      (libsource (lib "easyedapro") (part "螺丝孔"))
    )
    (comp (ref "TP30")
      (value "~")
      (footprint "easyedapro:Test-Point-0.5mm")
      (description "Test Point 测试点")
      (libsource (lib "easyedapro") (part "Test-Point"))
    )
    (comp (ref "TP31")
      (value "~")
      (footprint "easyedapro:Test-Point-0.5mm")
      (description "Test Point 测试点")
      (libsource (lib "easyedapro") (part "Test-Point"))
    )
    (comp (ref "TP32")
      (value "~")
      (footprint "easyedapro:螺丝孔")
      (description "内径3.0mm，外径4.5mm金属化螺丝孔")
      (libsource (lib "easyedapro") (part "螺丝孔"))
    )
    (comp (ref "TP33")
      (value "~")
      (footprint "easyedapro:螺丝孔")
      (description "内径3.0mm，外径4.5mm金属化螺丝孔")
      (libsource (lib "easyedapro") (part "螺丝孔"))
    )
    (comp (ref "TP34")
      (value "~")
      (footprint "easyedapro:螺丝孔")
      (description "内径3.0mm，外径4.5mm金属化螺丝孔")
      (libsource (lib "easyedapro") (part "螺丝孔"))
    )
    (comp (ref "TP35")
      (value "~")
      (footprint "easyedapro:螺丝孔")
      (description "内径3.0mm，外径4.5mm金属化螺丝孔")
      (libsource (lib "easyedapro") (part "螺丝孔"))
    )
    (comp (ref "U7")
      (value "CH340G")
      (footprint "easyedapro:SOIC-16_L9.9-W3.9-P1.27-LS6.0-BL")
      (description "类型:Transceiver;协议类别:USB 2.0;驱动器/接收器数:-;数据速率:2Mbps;")
      (fields (field (name "Manufacturer") "WCH(南京沁恒)"))
      (libsource (lib "easyedapro") (part "CH340G"))
    )
    (comp (ref "U8")
      (value "S8050")
      (footprint "easyedapro:SOT-23-3_L2.9-W1.3-P1.90-LS2.4")
      (fields (field (name "Manufacturer") "JUXING(钜兴)"))
      (libsource (lib "easyedapro") (part "S8050_C3011093"))
    )
    (comp (ref "U9")
      (value "PM254-2-04-W-8.5")
      (footprint "easyedapro:HDR-TH_8P-P2.54-H-F-R2-C4-W8.5")
      (fields (field (name "Manufacturer") "HCTL(华灿天禄)"))
      (libsource (lib "easyedapro") (part "PM254-2-04-W-8.5"))
    )
    (comp (ref "X1")
      (value "8MHz")
      (footprint "easyedapro:CRYSTAL-SMD_L11.5-W4.8-LS12.7")
      (description "晶振类型:49SMD;频率:8MHz;频率公差:±20ppm;频率稳定度:±30ppm;负载电容:20pF;工作温度:-20℃~+70℃;")
      (fields (field (name "Manufacturer Part") "X49SM8MSD2SC") (field (name "Manufacturer") "YXC(扬兴晶振)"))
      (libsource (lib "easyedapro") (part "X49SM8MSD2SC"))
    )
    (comp (ref "X2")
      (value "12MHz")
      (footprint "easyedapro:HC-49S_L11.4-W4.8")
      (description "晶振类型:49SMD;频率:12MHz;频率公差:±20ppm;频率稳定度:±30ppm;负载电容:20pF;工作温度:-20°C~+70°C;")
      (fields (field (name "Manufacturer Part") "X49SM12MSD2SC") (field (name "Manufacturer") "YXC(扬兴晶振)"))
      (libsource (lib "easyedapro") (part "X49SM12MSD2SC"))
    )
    (comp (ref "X3")
      (value "32.768kHz")
      (footprint "easyedapro:OSC-TH_BD2.0-P0.70-D0.3")
      (description "晶振类型:圆柱体晶振;频率:32.768kHz;频率公差:±10ppm;负载电容:12.5pF;工作温度:-20℃~+70℃;")
      (fields (field (name "Manufacturer Part") "X206032768KGB2SC") (field (name "Manufacturer") "YXC(扬兴晶振)"))
      (libsource (lib "easyedapro") (part "X206032768KGB2SC"))
    )
  )
  (nets
    (net (code "1") (name "-IN") (class "Default")
      (node (ref "R13") (pin "2") (pinfunction "2_2") (pintype "input"))
      (node (ref "R14") (pin "1") (pinfunction "1_1") (pintype "input"))
      (node (ref "U3") (pin "4") (pinfunction "-IN_4") (pintype "input"))
    )
    (net (code "2") (name "AGND") (class "Default")
      (node (ref "AGND") (pin "1") (pinfunction "1_1") (pintype "input"))
      (node (ref "C10") (pin "2") (pinfunction "2_2") (pintype "input"))
      (node (ref "C8") (pin "2") (pinfunction "2_2") (pintype "input"))
      (node (ref "C9") (pin "1") (pinfunction "1_1") (pintype "input"))
      (node (ref "L1") (pin "1") (pinfunction "1_1") (pintype "input"))
      (node (ref "U3") (pin "7") (pinfunction "GND_7") (pintype "input"))
    )
    (net (code "3") (name "BAT") (class "Default")
      (node (ref "C1") (pin "2") (pinfunction "2_2") (pintype "input"))
      (node (ref "C13") (pin "2") (pinfunction "2_2") (pintype "input"))
      (node (ref "C14") (pin "2") (pinfunction "2_2") (pintype "input"))
      (node (ref "C16") (pin "2") (pinfunction "2_2") (pintype "input"))
      (node (ref "C2") (pin "2") (pinfunction "2_2") (pintype "input"))
      (node (ref "CN1") (pin "1") (pinfunction "1_1") (pintype "input"))
      (node (ref "D1") (pin "1") (pinfunction "C_1") (pintype "input"))
      (node (ref "Q5") (pin "2") (pinfunction "S_2") (pintype "input"))
      (node (ref "R18") (pin "2") (pinfunction "2_2") (pintype "input"))
      (node (ref "R28") (pin "2") (pinfunction "2_2") (pintype "input"))
      (node (ref "R29") (pin "2") (pinfunction "2_2") (pintype "input"))
      (node (ref "R30") (pin "2") (pinfunction "2_2") (pintype "input"))
      (node (ref "TP1") (pin "1") (pinfunction "1_1") (pintype "input"))
      (node (ref "TP5") (pin "1") (pinfunction "1_1") (pintype "input"))
      (node (ref "U2") (pin "5") (pinfunction "BAT_5") (pintype "input"))
    )
    (net (code "4") (name "BAT_00_CTL") (class "Default")
      (node (ref "MCU1") (pin "36") (pinfunction "PB15_36") (pintype "input"))
      (node (ref "R59") (pin "1") (pinfunction "1_1") (pintype "input"))
    )
    (net (code "5") (name "BAT_25_CTL") (class "Default")
      (node (ref "MCU1") (pin "35") (pinfunction "PB14_35") (pintype "input"))
      (node (ref "R60") (pin "1") (pinfunction "1_1") (pintype "input"))
    )
    (net (code "6") (name "BAT_50_CTL") (class "Default")
      (node (ref "MCU1") (pin "34") (pinfunction "PB13_34") (pintype "input"))
      (node (ref "R61") (pin "1") (pinfunction "1_1") (pintype "input"))
    )
    (net (code "7") (name "BAT_75_CTL") (class "Default")
      (node (ref "MCU1") (pin "33") (pinfunction "PB12_33") (pintype "input"))
      (node (ref "R62") (pin "1") (pinfunction "1_1") (pintype "input"))
    )
    (net (code "8") (name "BOOT0") (class "Default")
      (node (ref "MCU1") (pin "60") (pinfunction "BOO_T0_60") (pintype "input"))
      (node (ref "R48") (pin "2") (pinfunction "2_2") (pintype "input"))
    )
    (net (code "9") (name "BOOT1") (class "Default")
      (node (ref "R73") (pin "2") (pinfunction "2_2") (pintype "input"))
      (node (ref "R74") (pin "1") (pinfunction "1_1") (pintype "input"))
    )
    (net (code "10") (name "CH340_D+") (class "Default")
      (node (ref "R3") (pin "2") (pinfunction "2_2") (pintype "input"))
      (node (ref "U7") (pin "5") (pinfunction "UD+_5") (pintype "input"))
      (node (ref "USB1") (pin "3") (pinfunction "D+_3") (pintype "input"))
    )
    (net (code "11") (name "CH340_D-") (class "Default")
      (node (ref "U7") (pin "6") (pinfunction "UD-_6") (pintype "input"))
      (node (ref "USB1") (pin "2") (pinfunction "D-_2") (pintype "input"))
    )
    (net (code "12") (name "CHRG") (class "Default")
      (node (ref "R9") (pin "1") (pinfunction "1_1") (pintype "input"))
      (node (ref "U2") (pin "7") (pinfunction "CHRG#_7") (pintype "input"))
    )
    (net (code "13") (name "DIAN_LIANG") (class "Default")
      (node (ref "MCU1") (pin "17") (pinfunction "PA3_17") (pintype "input"))
      (node (ref "R20") (pin "2") (pinfunction "2_2") (pintype "input"))
    )
    (net (code "14") (name "GND") (class "Default")
      (node (ref "C1") (pin "1") (pinfunction "1_1") (pintype "input"))
      (node (ref "C12") (pin "1") (pinfunction "1_1") (pintype "input"))
      (node (ref "C17") (pin "2") (pinfunction "2_2") (pintype "input"))
      (node (ref "C18") (pin "1") (pinfunction "1_1") (pintype "input"))
      (node (ref "C19") (pin "1") (pinfunction "1_1") (pintype "input"))
      (node (ref "C2") (pin "1") (pinfunction "1_1") (pintype "input"))
      (node (ref "C20") (pin "2") (pinfunction "2_2") (pintype "input"))
      (node (ref "C21") (pin "2") (pinfunction "2_2") (pintype "input"))
      (node (ref "C22") (pin "1") (pinfunction "1_1") (pintype "input"))
      (node (ref "C23") (pin "1") (pinfunction "1_1") (pintype "input"))
      (node (ref "C24") (pin "2") (pinfunction "2_2") (pintype "input"))
      (node (ref "C25") (pin "2") (pinfunction "2_2") (pintype "input"))
      (node (ref "C26") (pin "1") (pinfunction "1_1") (pintype "input"))
      (node (ref "C27") (pin "1") (pinfunction "1_1") (pintype "input"))
      (node (ref "C28") (pin "2") (pinfunction "2_2") (pintype "input"))
      (node (ref "C29") (pin "1") (pinfunction "1_1") (pintype "input"))
      (node (ref "C3") (pin "2") (pinfunction "2_2") (pintype "input"))
      (node (ref "C30") (pin "1") (pinfunction "1_1") (pintype "input"))
      (node (ref "C31") (pin "2") (pinfunction "2_2") (pintype "input"))
      (node (ref "C32") (pin "2") (pinfunction "2_2") (pintype "input"))
      (node (ref "C33") (pin "2") (pinfunction "2_2") (pintype "input"))
      (node (ref "C34") (pin "2") (pinfunction "2_2") (pintype "input"))
      (node (ref "C35") (pin "2") (pinfunction "2_2") (pintype "input"))
      (node (ref "C36") (pin "2") (pinfunction "2_2") (pintype "input"))
      (node (ref "C37") (pin "1") (pinfunction "1_1") (pintype "input"))
      (node (ref "C38") (pin "1") (pinfunction "1_1") (pintype "input"))
      (node (ref "C39") (pin "2") (pinfunction "2_2") (pintype "input"))
      (node (ref "C4") (pin "2") (pinfunction "2_2") (pintype "input"))
      (node (ref "C40") (pin "1") (pinfunction "1_1") (pintype "input"))
      (node (ref "C41") (pin "1") (pinfunction "1_1") (pintype "input"))
      (node (ref "C42") (pin "1") (pinfunction "1_1") (pintype "input"))
      (node (ref "C43") (pin "2") (pinfunction "2_2") (pintype "input"))
      (node (ref "C44") (pin "1") (pinfunction "1_1") (pintype "input"))
      (node (ref "C45") (pin "1") (pinfunction "1_1") (pintype "input"))
      (node (ref "C46") (pin "1") (pinfunction "1_1") (pintype "input"))
      (node (ref "C47") (pin "1") (pinfunction "1_1") (pintype "input"))
      (node (ref "C48") (pin "1") (pinfunction "1_1") (pintype "input"))
      (node (ref "C49") (pin "1") (pinfunction "1_1") (pintype "input"))
      (node (ref "C50") (pin "1") (pinfunction "1_1") (pintype "input"))
      (node (ref "C51") (pin "1") (pinfunction "1_1") (pintype "input"))
      (node (ref "C52") (pin "1") (pinfunction "1_1") (pintype "input"))
      (node (ref "C53") (pin "1") (pinfunction "1_1") (pintype "input"))
      (node (ref "C54") (pin "1") (pinfunction "1_1") (pintype "input"))
      (node (ref "C55") (pin "1") (pinfunction "1_1") (pintype "input"))
      (node (ref "C56") (pin "1") (pinfunction "1_1") (pintype "input"))
      (node (ref "C58") (pin "2") (pinfunction "2_2") (pintype "input"))
      (node (ref "C7") (pin "1") (pinfunction "1_1") (pintype "input"))
      (node (ref "CN1") (pin "2") (pinfunction "2_2") (pintype "input"))
      (node (ref "D1") (pin "2") (pinfunction "A_2") (pintype "input"))
      (node (ref "D10") (pin "2") (pinfunction "K_2") (pintype "input"))
      (node (ref "D2") (pin "2") (pinfunction "A_2") (pintype "input"))
      (node (ref "D7") (pin "2") (pinfunction "K_2") (pintype "input"))
      (node (ref "D8") (pin "2") (pinfunction "K_2") (pintype "input"))
      (node (ref "D9") (pin "2") (pinfunction "K_2") (pintype "input"))
      (node (ref "E1") (pin "2") (pinfunction "2_2") (pintype "input"))
      (node (ref "E10") (pin "2") (pinfunction "2_2") (pintype "input"))
      (node (ref "E2") (pin "2") (pinfunction "2_2") (pintype "input"))
      (node (ref "E3") (pin "2") (pinfunction "2_2") (pintype "input"))
      (node (ref "E4") (pin "2") (pinfunction "2_2") (pintype "input"))
      (node (ref "E5") (pin "2") (pinfunction "2_2") (pintype "input"))
      (node (ref "E6") (pin "2") (pinfunction "2_2") (pintype "input"))
      (node (ref "E7") (pin "2") (pinfunction "2_2") (pintype "input"))
      (node (ref "E8") (pin "2") (pinfunction "2_2") (pintype "input"))
      (node (ref "E9") (pin "2") (pinfunction "2_2") (pintype "input"))
      (node (ref "GND") (pin "1") (pinfunction "1_1") (pintype "input"))
      (node (ref "H2") (pin "2") (pinfunction "2_2") (pintype "input"))
      (node (ref "H3") (pin "2") (pinfunction "2_2") (pintype "input"))
      (node (ref "H4") (pin "2") (pinfunction "2_2") (pintype "input"))
      (node (ref "I1") (pin "7") (pinfunction "7_7") (pintype "input"))
      (node (ref "K1") (pin "1") (pinfunction "1_1") (pintype "input"))
      (node (ref "K2") (pin "1") (pinfunction "1_1") (pintype "input"))
      (node (ref "K3") (pin "1") (pinfunction "1_1") (pintype "input"))
      (node (ref "K4") (pin "1") (pinfunction "1_1") (pintype "input"))
      (node (ref "K5") (pin "1") (pinfunction "1_1") (pintype "input"))
      (node (ref "K6") (pin "1") (pinfunction "1_1") (pintype "input"))
      (node (ref "Krest") (pin "2") (pinfunction "2_2") (pintype "input"))
      (node (ref "L1") (pin "2") (pinfunction "2_2") (pintype "input"))
      (node (ref "LED3") (pin "1") (pinfunction "K_1") (pintype "input"))
      (node (ref "LED4") (pin "1") (pinfunction "K_1") (pintype "input"))
      (node (ref "LED5") (pin "1") (pinfunction "K_1") (pintype "input"))
      (node (ref "MCU1") (pin "12") (pinfunction "VSSA_12") (pintype "input"))
      (node (ref "MCU1") (pin "18") (pinfunction "VSS_4_18") (pintype "input"))
      (node (ref "MCU1") (pin "31") (pinfunction "VSS_1_31") (pintype "input"))
      (node (ref "MCU1") (pin "47") (pinfunction "VSS_2_47") (pintype "input"))
      (node (ref "MCU1") (pin "63") (pinfunction "VSS_3_63") (pintype "input"))
      (node (ref "Q10") (pin "2") (pinfunction "S_2") (pintype "input"))
      (node (ref "Q2") (pin "2") (pinfunction "S_2") (pintype "input"))
      (node (ref "Q4") (pin "2") (pinfunction "S_2") (pintype "input"))
      (node (ref "Q7") (pin "2") (pinfunction "S_2") (pintype "input"))
      (node (ref "R1") (pin "1") (pinfunction "1_1") (pintype "input"))
      (node (ref "R21") (pin "1") (pinfunction "1_1") (pintype "input"))
      (node (ref "R23") (pin "2") (pinfunction "2_2") (pintype "input"))
      (node (ref "R27") (pin "1") (pinfunction "1_1") (pintype "input"))
      (node (ref "R39") (pin "1") (pinfunction "1_1") (pintype "input"))
      (node (ref "R4") (pin "2") (pinfunction "2_2") (pintype "input"))
      (node (ref "R42") (pin "1") (pinfunction "1_1") (pintype "input"))
      (node (ref "R49") (pin "1") (pinfunction "1_1") (pintype "input"))
      (node (ref "R7") (pin "1") (pinfunction "1_1") (pintype "input"))
      (node (ref "R74") (pin "2") (pinfunction "2_2") (pintype "input"))
      (node (ref "R78") (pin "1") (pinfunction "1_1") (pintype "input"))
      (node (ref "R79") (pin "2") (pinfunction "2_2") (pintype "input"))
      (node (ref "SW1") (pin "(3)") (pinfunction "(3)_(3)") (pintype "input"))
      (node (ref "SW1") (pin "3") (pinfunction "3_3") (pintype "input"))
      (node (ref "SW2") (pin "(3)") (pinfunction "(3)_(3)") (pintype "input"))
      (node (ref "SW2") (pin "3") (pinfunction "3_3") (pintype "input"))
      (node (ref "T1") (pin "7") (pinfunction "7_7") (pintype "input"))
      (node (ref "TP26") (pin "1") (pinfunction "1_1") (pintype "input"))
      (node (ref "TP27") (pin "1") (pinfunction "1_1") (pintype "input"))
      (node (ref "TP28") (pin "1") (pinfunction "1_1") (pintype "input"))
      (node (ref "TP29") (pin "1") (pinfunction "1_1") (pintype "input"))
      (node (ref "TP32") (pin "1") (pinfunction "1_1") (pintype "input"))
      (node (ref "TP33") (pin "1") (pinfunction "1_1") (pintype "input"))
      (node (ref "TP34") (pin "1") (pinfunction "1_1") (pintype "input"))
      (node (ref "TP35") (pin "1") (pinfunction "1_1") (pintype "input"))
      (node (ref "U2") (pin "3") (pinfunction "GND_3") (pintype "input"))
      (node (ref "U2") (pin "9") (pinfunction "EP_9") (pintype "input"))
      (node (ref "U4") (pin "2") (pinfunction "GND_2") (pintype "input"))
      (node (ref "U5") (pin "2") (pinfunction "GND_2") (pintype "input"))
      (node (ref "U6") (pin "2") (pinfunction "GND_2") (pintype "input"))
      (node (ref "U7") (pin "1") (pinfunction "GND_1") (pintype "input"))
      (node (ref "U9") (pin "4") (pinfunction "4_4") (pintype "unspecified"))
      (node (ref "USB1") (pin "0") (pinfunction "SHLD_0") (pintype "input"))
      (node (ref "USB1") (pin "5") (pinfunction "GND_5") (pintype "input"))
      (node (ref "开关") (pin "1") (pinfunction "1_1") (pintype "input"))
    )
    (net (code "15") (name "I2C2_SCL") (class "Default")
      (node (ref "I1") (pin "6") (pinfunction "6_6") (pintype "input"))
      (node (ref "MCU1") (pin "29") (pinfunction "PB10_29") (pintype "input"))
      (node (ref "TP16") (pin "1") (pinfunction "1_1") (pintype "input"))
    )
    (net (code "16") (name "I2C2_SDA") (class "Default")
      (node (ref "I1") (pin "5") (pinfunction "5_5") (pintype "input"))
      (node (ref "MCU1") (pin "30") (pinfunction "PB11_30") (pintype "input"))
      (node (ref "TP15") (pin "1") (pinfunction "1_1") (pintype "input"))
    )
    (net (code "17") (name "K1") (class "Default")
      (node (ref "C45") (pin "2") (pinfunction "2_2") (pintype "input"))
      (node (ref "K1") (pin "2") (pinfunction "2_2") (pintype "input"))
      (node (ref "MCU1") (pin "8") (pinfunction "PC0_8") (pintype "input"))
      (node (ref "R63") (pin "1") (pinfunction "1_1") (pintype "input"))
    )
    (net (code "18") (name "K2") (class "Default")
      (node (ref "C48") (pin "2") (pinfunction "2_2") (pintype "input"))
      (node (ref "K2") (pin "2") (pinfunction "2_2") (pintype "input"))
      (node (ref "MCU1") (pin "9") (pinfunction "PC1_9") (pintype "input"))
      (node (ref "R66") (pin "1") (pinfunction "1_1") (pintype "input"))
    )
    (net (code "19") (name "K3") (class "Default")
      (node (ref "C46") (pin "2") (pinfunction "2_2") (pintype "input"))
      (node (ref "K3") (pin "2") (pinfunction "2_2") (pintype "input"))
      (node (ref "MCU1") (pin "10") (pinfunction "PC2_10") (pintype "input"))
      (node (ref "R64") (pin "1") (pinfunction "1_1") (pintype "input"))
    )
    (net (code "20") (name "K4") (class "Default")
      (node (ref "C49") (pin "2") (pinfunction "2_2") (pintype "input"))
      (node (ref "K4") (pin "2") (pinfunction "2_2") (pintype "input"))
      (node (ref "MCU1") (pin "11") (pinfunction "PC3_11") (pintype "input"))
      (node (ref "R67") (pin "1") (pinfunction "1_1") (pintype "input"))
    )
    (net (code "21") (name "K5") (class "Default")
      (node (ref "C47") (pin "2") (pinfunction "2_2") (pintype "input"))
      (node (ref "K5") (pin "2") (pinfunction "2_2") (pintype "input"))
      (node (ref "MCU1") (pin "40") (pinfunction "PC9_40") (pintype "input"))
      (node (ref "R65") (pin "1") (pinfunction "1_1") (pintype "input"))
    )
    (net (code "22") (name "K6") (class "Default")
      (node (ref "C50") (pin "2") (pinfunction "2_2") (pintype "input"))
      (node (ref "K6") (pin "2") (pinfunction "2_2") (pintype "input"))
      (node (ref "MCU1") (pin "39") (pinfunction "PC8_39") (pintype "input"))
      (node (ref "R68") (pin "1") (pinfunction "1_1") (pintype "input"))
    )
    (net (code "23") (name "LEFT_Q") (class "Default")
      (node (ref "MCU1") (pin "15") (pinfunction "PA1_15") (pintype "input"))
      (node (ref "R11") (pin "1") (pinfunction "1_1") (pintype "input"))
    )
    (net (code "24") (name "LEFT_Z") (class "Default")
      (node (ref "MCU1") (pin "16") (pinfunction "PA2_16") (pintype "input"))
      (node (ref "R12") (pin "1") (pinfunction "1_1") (pintype "input"))
    )
    (net (code "25") (name "MOT_L") (class "Default")
      (node (ref "MCU1") (pin "38") (pinfunction "PC7_38") (pintype "input"))
      (node (ref "R19") (pin "2") (pinfunction "2_2") (pintype "input"))
    )
    (net (code "26") (name "MOT_R") (class "Default")
      (node (ref "MCU1") (pin "37") (pinfunction "PC6_37") (pintype "input"))
      (node (ref "R26") (pin "2") (pinfunction "2_2") (pintype "input"))
    )
    (net (code "27") (name "Net-(C5-Pad1)") (class "Default")
      (node (ref "C5") (pin "1") (pinfunction "1_1") (pintype "input"))
      (node (ref "R13") (pin "1") (pinfunction "1_1") (pintype "input"))
    )
    (net (code "28") (name "Net-(C15-Pad1)") (class "Default")
      (node (ref "C15") (pin "1") (pinfunction "1_1") (pintype "input"))
      (node (ref "R32") (pin "2") (pinfunction "2_2") (pintype "input"))
    )
    (net (code "29") (name "Net-(C26-Pad2)") (class "Default")
      (node (ref "C26") (pin "2") (pinfunction "2_2") (pintype "input"))
      (node (ref "C27") (pin "2") (pinfunction "2_2") (pintype "input"))
      (node (ref "R40") (pin "1") (pinfunction "1_1") (pintype "input"))
      (node (ref "R41") (pin "1") (pinfunction "1_1") (pintype "input"))
      (node (ref "R42") (pin "2") (pinfunction "2_2") (pintype "input"))
      (node (ref "TP12") (pin "1") (pinfunction "1_1") (pintype "input"))
    )
    (net (code "30") (name "Net-(D2-K)") (class "Default")
      (node (ref "5V") (pin "1") (pinfunction "1_1") (pintype "input"))
      (node (ref "D2") (pin "1") (pinfunction "K_1") (pintype "input"))
      (node (ref "U1") (pin "1") (pinfunction "1_1") (pintype "input"))
      (node (ref "USB1") (pin "1") (pinfunction "VCC_1") (pintype "input"))
    )
    (net (code "31") (name "Net-(D3-A)") (class "Default")
      (node (ref "D3") (pin "2") (pinfunction "A_2") (pintype "input"))
      (node (ref "R33") (pin "1") (pinfunction "1_1") (pintype "input"))
      (node (ref "R35") (pin "2") (pinfunction "2_2") (pintype "input"))
    )
    (net (code "32") (name "Net-(D3-C)") (class "Default")
      (node (ref "C25") (pin "1") (pinfunction "1_1") (pintype "input"))
      (node (ref "D3") (pin "1") (pinfunction "C_1") (pintype "input"))
      (node (ref "D4") (pin "2") (pinfunction "A_2") (pintype "input"))
      (node (ref "D5") (pin "1") (pinfunction "C_1") (pintype "input"))
      (node (ref "R28") (pin "1") (pinfunction "1_1") (pintype "input"))
      (node (ref "TP11") (pin "1") (pinfunction "1_1") (pintype "input"))
      (node (ref "开关") (pin "4") (pinfunction "4_4") (pintype "input"))
    )
    (net (code "33") (name "Net-(D4-C)") (class "Default")
      (node (ref "C13") (pin "1") (pinfunction "1_1") (pintype "input"))
      (node (ref "C14") (pin "1") (pinfunction "1_1") (pintype "input"))
      (node (ref "D4") (pin "1") (pinfunction "C_1") (pintype "input"))
      (node (ref "R36") (pin "1") (pinfunction "1_1") (pintype "input"))
      (node (ref "TP9") (pin "1") (pinfunction "1_1") (pintype "input"))
    )
    (net (code "34") (name "Net-(D5-A)") (class "Default")
      (node (ref "D5") (pin "2") (pinfunction "A_2") (pintype "input"))
      (node (ref "Q6") (pin "2") (pinfunction "S_2") (pintype "input"))
      (node (ref "Q7") (pin "3") (pinfunction "D_3") (pintype "input"))
      (node (ref "R29") (pin "1") (pinfunction "1_1") (pintype "input"))
      (node (ref "R37") (pin "1") (pinfunction "1_1") (pintype "input"))
      (node (ref "TP13") (pin "1") (pinfunction "1_1") (pintype "input"))
    )
    (net (code "35") (name "Net-(D6-K)") (class "Default")
      (node (ref "D6") (pin "1") (pinfunction "K_1") (pintype "input"))
      (node (ref "R44") (pin "1") (pinfunction "1_1") (pintype "input"))
      (node (ref "U8") (pin "3") (pinfunction "C_3") (pintype "input"))
    )
    (net (code "36") (name "Net-(LED1-K)") (class "Default")
      (node (ref "LED1") (pin "2") (pinfunction "K_2") (pintype "input"))
      (node (ref "R9") (pin "2") (pinfunction "2_2") (pintype "input"))
    )
    (net (code "37") (name "Net-(LED2-K)") (class "Default")
      (node (ref "LED2") (pin "1") (pinfunction "K_1") (pintype "input"))
      (node (ref "R10") (pin "2") (pinfunction "2_2") (pintype "input"))
    )
    (net (code "38") (name "Net-(LED3-A)") (class "Default")
      (node (ref "LED3") (pin "2") (pinfunction "A_2") (pintype "input"))
      (node (ref "R31") (pin "1") (pinfunction "1_1") (pintype "input"))
    )
    (net (code "39") (name "Net-(LED4-A)") (class "Default")
      (node (ref "LED4") (pin "2") (pinfunction "A_2") (pintype "input"))
      (node (ref "R38") (pin "1") (pinfunction "1_1") (pintype "input"))
    )
    (net (code "40") (name "Net-(LED5-A)") (class "Default")
      (node (ref "LED5") (pin "2") (pinfunction "A_2") (pintype "input"))
      (node (ref "R43") (pin "1") (pinfunction "1_1") (pintype "input"))
    )
    (net (code "41") (name "Net-(LED6-Pad1)") (class "Default")
      (node (ref "LED6") (pin "1") (pinfunction "1_1") (pintype "input"))
      (node (ref "R58") (pin "2") (pinfunction "2_2") (pintype "input"))
    )
    (net (code "42") (name "Net-(LED6-Pad2)") (class "Default")
      (node (ref "LED6") (pin "2") (pinfunction "2_2") (pintype "input"))
      (node (ref "R57") (pin "2") (pinfunction "2_2") (pintype "input"))
    )
    (net (code "43") (name "Net-(LED6-Pad4)") (class "Default")
      (node (ref "LED6") (pin "4") (pinfunction "4_4") (pintype "input"))
      (node (ref "R56") (pin "2") (pinfunction "2_2") (pintype "input"))
    )
    (net (code "44") (name "Net-(LED7-K)") (class "Default")
      (node (ref "LED7") (pin "2") (pinfunction "K_2") (pintype "input"))
      (node (ref "R59") (pin "2") (pinfunction "2_2") (pintype "input"))
    )
    (net (code "45") (name "Net-(LED8-K)") (class "Default")
      (node (ref "LED8") (pin "2") (pinfunction "K_2") (pintype "input"))
      (node (ref "R60") (pin "2") (pinfunction "2_2") (pintype "input"))
    )
    (net (code "46") (name "Net-(LED9-K)") (class "Default")
      (node (ref "LED9") (pin "2") (pinfunction "K_2") (pintype "input"))
      (node (ref "R61") (pin "2") (pinfunction "2_2") (pintype "input"))
    )
    (net (code "47") (name "Net-(LED10-K)") (class "Default")
      (node (ref "LED10") (pin "2") (pinfunction "K_2") (pintype "input"))
      (node (ref "R62") (pin "2") (pinfunction "2_2") (pintype "input"))
    )
    (net (code "48") (name "Net-(MCU1-PA0-WKUP)") (class "Default")
      (node (ref "MCU1") (pin "14") (pinfunction "PA0-WKUP_14") (pintype "input"))
      (node (ref "TP20") (pin "1") (pinfunction "1_1") (pintype "input"))
    )
    (net (code "49") (name "Net-(MCU1-PA6)") (class "Default")
      (node (ref "MCU1") (pin "22") (pinfunction "PA6_22") (pintype "input"))
      (node (ref "TP23") (pin "1") (pinfunction "1_1") (pintype "input"))
    )
    (net (code "50") (name "Net-(MCU1-PA13)") (class "Default")
      (node (ref "MCU1") (pin "46") (pinfunction "PA13_46") (pintype "input"))
      (node (ref "R72") (pin "1") (pinfunction "1_1") (pintype "input"))
    )
    (net (code "51") (name "Net-(MCU1-PA14)") (class "Default")
      (node (ref "MCU1") (pin "49") (pinfunction "PA14_49") (pintype "input"))
      (node (ref "R71") (pin "1") (pinfunction "1_1") (pintype "input"))
    )
    (net (code "52") (name "Net-(MCU1-PA15)") (class "Default")
      (node (ref "MCU1") (pin "50") (pinfunction "PA15_50") (pintype "input"))
      (node (ref "TP22") (pin "1") (pinfunction "1_1") (pintype "input"))
    )
    (net (code "53") (name "Net-(MCU1-PB0)") (class "Default")
      (node (ref "MCU1") (pin "26") (pinfunction "PB0_26") (pintype "input"))
      (node (ref "TP24") (pin "1") (pinfunction "1_1") (pintype "input"))
    )
    (net (code "54") (name "Net-(MCU1-PB1)") (class "Default")
      (node (ref "MCU1") (pin "27") (pinfunction "PB1_27") (pintype "input"))
      (node (ref "TP25") (pin "1") (pinfunction "1_1") (pintype "input"))
    )
    (net (code "55") (name "Net-(MCU1-PB2)") (class "Default")
      (node (ref "MCU1") (pin "28") (pinfunction "PB2_28") (pintype "input"))
      (node (ref "R73") (pin "1") (pinfunction "1_1") (pintype "input"))
    )
    (net (code "56") (name "Net-(MCU1-PB3)") (class "Default")
      (node (ref "MCU1") (pin "55") (pinfunction "PB3_55") (pintype "input"))
      (node (ref "TP19") (pin "1") (pinfunction "1_1") (pintype "input"))
    )
    (net (code "57") (name "Net-(MCU1-PB4)") (class "Default")
      (node (ref "MCU1") (pin "56") (pinfunction "PB4_56") (pintype "input"))
      (node (ref "R53") (pin "1") (pinfunction "1_1") (pintype "input"))
    )
    (net (code "58") (name "Net-(MCU1-PB5)") (class "Default")
      (node (ref "MCU1") (pin "57") (pinfunction "PB5_57") (pintype "input"))
      (node (ref "R54") (pin "1") (pinfunction "1_1") (pintype "input"))
    )
    (net (code "59") (name "Net-(MCU1-PB6)") (class "Default")
      (node (ref "MCU1") (pin "58") (pinfunction "PB6_58") (pintype "input"))
      (node (ref "R55") (pin "1") (pinfunction "1_1") (pintype "input"))
    )
    (net (code "60") (name "Net-(MCU1-PB7)") (class "Default")
      (node (ref "MCU1") (pin "59") (pinfunction "PB7_59") (pintype "input"))
      (node (ref "R52") (pin "1") (pinfunction "1_1") (pintype "input"))
    )
    (net (code "61") (name "Net-(MCU1-PB8)") (class "Default")
      (node (ref "MCU1") (pin "61") (pinfunction "PB8_61") (pintype "input"))
      (node (ref "R50") (pin "1") (pinfunction "1_1") (pintype "input"))
    )
    (net (code "62") (name "Net-(MCU1-PB9)") (class "Default")
      (node (ref "MCU1") (pin "62") (pinfunction "PB9_62") (pintype "input"))
      (node (ref "R51") (pin "1") (pinfunction "1_1") (pintype "input"))
    )
    (net (code "63") (name "Net-(MCU1-PC10)") (class "Default")
      (node (ref "MCU1") (pin "51") (pinfunction "PC10_51") (pintype "input"))
      (node (ref "R70") (pin "1") (pinfunction "1_1") (pintype "input"))
    )
    (net (code "64") (name "Net-(MCU1-PC11)") (class "Default")
      (node (ref "MCU1") (pin "52") (pinfunction "PC11_52") (pintype "input"))
      (node (ref "R69") (pin "1") (pinfunction "1_1") (pintype "input"))
    )
    (net (code "65") (name "Net-(MCU1-PC12)") (class "Default")
      (node (ref "MCU1") (pin "53") (pinfunction "PC12_53") (pintype "input"))
      (node (ref "TP21") (pin "1") (pinfunction "1_1") (pintype "input"))
    )
    (net (code "66") (name "Net-(MCU1-PC13-TAMPER-RTC)") (class "Default")
      (node (ref "MCU1") (pin "2") (pinfunction "PC13-TAMPER-RTC_2") (pintype "input"))
      (node (ref "TP18") (pin "1") (pinfunction "1_1") (pintype "input"))
    )
    (net (code "67") (name "Net-(MCU1-VBAT)") (class "Default")
      (node (ref "MCU1") (pin "1") (pinfunction "VBAT_1") (pintype "input"))
      (node (ref "TP17") (pin "1") (pinfunction "1_1") (pintype "input"))
    )
    (net (code "68") (name "Net-(Q1-D)") (class "Default")
      (node (ref "H2") (pin "1") (pinfunction "1_1") (pintype "input"))
      (node (ref "Q1") (pin "3") (pinfunction "D_3") (pintype "input"))
    )
    (net (code "69") (name "Net-(Q1-G)") (class "Default")
      (node (ref "C6") (pin "2") (pinfunction "2_2") (pintype "input"))
      (node (ref "Q1") (pin "1") (pinfunction "G_1") (pintype "input"))
      (node (ref "R16") (pin "1") (pinfunction "1_1") (pintype "input"))
      (node (ref "R17") (pin "2") (pinfunction "2_2") (pintype "input"))
    )
    (net (code "70") (name "Net-(Q2-D)") (class "Default")
      (node (ref "Q2") (pin "3") (pinfunction "D_3") (pintype "input"))
      (node (ref "R17") (pin "1") (pinfunction "1_1") (pintype "input"))
    )
    (net (code "71") (name "Net-(Q2-G)") (class "Default")
      (node (ref "C7") (pin "2") (pinfunction "2_2") (pintype "input"))
      (node (ref "Q2") (pin "1") (pinfunction "G_1") (pintype "input"))
      (node (ref "R19") (pin "1") (pinfunction "1_1") (pintype "input"))
      (node (ref "R21") (pin "2") (pinfunction "2_2") (pintype "input"))
    )
    (net (code "72") (name "Net-(Q3-D)") (class "Default")
      (node (ref "H3") (pin "1") (pinfunction "1_1") (pintype "input"))
      (node (ref "Q3") (pin "3") (pinfunction "D_3") (pintype "input"))
    )
    (net (code "73") (name "Net-(Q3-G)") (class "Default")
      (node (ref "C11") (pin "2") (pinfunction "2_2") (pintype "input"))
      (node (ref "Q3") (pin "1") (pinfunction "G_1") (pintype "input"))
      (node (ref "R24") (pin "1") (pinfunction "1_1") (pintype "input"))
      (node (ref "R25") (pin "2") (pinfunction "2_2") (pintype "input"))
    )
    (net (code "74") (name "Net-(Q4-D)") (class "Default")
      (node (ref "Q4") (pin "3") (pinfunction "D_3") (pintype "input"))
      (node (ref "R25") (pin "1") (pinfunction "1_1") (pintype "input"))
    )
    (net (code "75") (name "Net-(Q4-G)") (class "Default")
      (node (ref "C12") (pin "2") (pinfunction "2_2") (pintype "input"))
      (node (ref "Q4") (pin "1") (pinfunction "G_1") (pintype "input"))
      (node (ref "R26") (pin "1") (pinfunction "1_1") (pintype "input"))
      (node (ref "R27") (pin "2") (pinfunction "2_2") (pintype "input"))
    )
    (net (code "76") (name "Net-(Q5-G)") (class "Default")
      (node (ref "C16") (pin "1") (pinfunction "1_1") (pintype "input"))
      (node (ref "Q5") (pin "1") (pinfunction "G_1") (pintype "input"))
      (node (ref "R30") (pin "1") (pinfunction "1_1") (pintype "input"))
      (node (ref "R32") (pin "1") (pinfunction "1_1") (pintype "input"))
      (node (ref "R34") (pin "2") (pinfunction "2_2") (pintype "input"))
    )
    (net (code "77") (name "Net-(Q6-D)") (class "Default")
      (node (ref "Q6") (pin "3") (pinfunction "D_3") (pintype "input"))
      (node (ref "R34") (pin "1") (pinfunction "1_1") (pintype "input"))
      (node (ref "R39") (pin "2") (pinfunction "2_2") (pintype "input"))
      (node (ref "TP8") (pin "1") (pinfunction "1_1") (pintype "input"))
    )
    (net (code "78") (name "Net-(Q6-G)") (class "Default")
      (node (ref "Q6") (pin "1") (pinfunction "G_1") (pintype "input"))
      (node (ref "R36") (pin "2") (pinfunction "2_2") (pintype "input"))
      (node (ref "R37") (pin "2") (pinfunction "2_2") (pintype "input"))
      (node (ref "TP10") (pin "1") (pinfunction "1_1") (pintype "input"))
    )
    (net (code "79") (name "Net-(Q7-G)") (class "Default")
      (node (ref "Q7") (pin "1") (pinfunction "G_1") (pintype "input"))
      (node (ref "R41") (pin "2") (pinfunction "2_2") (pintype "input"))
    )
    (net (code "80") (name "Net-(Q8-B)") (class "Default")
      (node (ref "Q8") (pin "1") (pinfunction "B_1") (pintype "input"))
      (node (ref "R47") (pin "2") (pinfunction "2_2") (pintype "input"))
    )
    (net (code "81") (name "Net-(Q8-C)") (class "Default")
      (node (ref "Q8") (pin "3") (pinfunction "C_3") (pintype "input"))
      (node (ref "R48") (pin "1") (pinfunction "1_1") (pintype "input"))
      (node (ref "R49") (pin "2") (pinfunction "2_2") (pintype "input"))
    )
    (net (code "82") (name "Net-(Q9-G)") (class "Default")
      (node (ref "C57") (pin "2") (pinfunction "2_2") (pintype "input"))
      (node (ref "Q9") (pin "1") (pinfunction "G_1") (pintype "input"))
      (node (ref "R75") (pin "2") (pinfunction "2_2") (pintype "input"))
      (node (ref "R76") (pin "1") (pinfunction "1_1") (pintype "input"))
      (node (ref "TP30") (pin "1") (pinfunction "1_1") (pintype "input"))
    )
    (net (code "83") (name "Net-(Q10-D)") (class "Default")
      (node (ref "Q10") (pin "3") (pinfunction "D_3") (pintype "input"))
      (node (ref "R76") (pin "2") (pinfunction "2_2") (pintype "input"))
      (node (ref "R78") (pin "2") (pinfunction "2_2") (pintype "input"))
    )
    (net (code "84") (name "Net-(Q10-G)") (class "Default")
      (node (ref "C58") (pin "1") (pinfunction "1_1") (pintype "input"))
      (node (ref "Q10") (pin "1") (pinfunction "G_1") (pintype "input"))
      (node (ref "R77") (pin "2") (pinfunction "2_2") (pintype "input"))
      (node (ref "R79") (pin "1") (pinfunction "1_1") (pintype "input"))
      (node (ref "TP31") (pin "1") (pinfunction "1_1") (pintype "input"))
    )
    (net (code "85") (name "Net-(R5-Pad2)") (class "Default")
      (node (ref "R5") (pin "2") (pinfunction "2_2") (pintype "input"))
      (node (ref "SW1") (pin "(2)") (pinfunction "(2)_(2)") (pintype "input"))
    )
    (net (code "86") (name "Net-(R6-Pad2)") (class "Default")
      (node (ref "R6") (pin "2") (pinfunction "2_2") (pintype "input"))
      (node (ref "SW1") (pin "2") (pinfunction "2_2") (pintype "input"))
    )
    (net (code "87") (name "Net-(R11-Pad2)") (class "Default")
      (node (ref "R11") (pin "2") (pinfunction "2_2") (pintype "input"))
      (node (ref "SW2") (pin "(2)") (pinfunction "(2)_(2)") (pintype "input"))
    )
    (net (code "88") (name "Net-(R12-Pad2)") (class "Default")
      (node (ref "R12") (pin "2") (pinfunction "2_2") (pintype "input"))
      (node (ref "SW2") (pin "2") (pinfunction "2_2") (pintype "input"))
    )
    (net (code "89") (name "Net-(R14-Pad2)") (class "Default")
      (node (ref "R14") (pin "2") (pinfunction "2_2") (pintype "input"))
      (node (ref "R15") (pin "2") (pinfunction "2_2") (pintype "input"))
    )
    (net (code "90") (name "Net-(R18-Pad1)") (class "Default")
      (node (ref "R18") (pin "1") (pinfunction "1_1") (pintype "input"))
      (node (ref "R20") (pin "1") (pinfunction "1_1") (pintype "input"))
      (node (ref "R23") (pin "1") (pinfunction "1_1") (pintype "input"))
    )
    (net (code "91") (name "Net-(U2-CE)") (class "Default")
      (node (ref "R8") (pin "1") (pinfunction "1_1") (pintype "input"))
      (node (ref "U2") (pin "8") (pinfunction "CE_8") (pintype "input"))
    )
    (net (code "92") (name "Net-(U2-PROG)") (class "Default")
      (node (ref "R7") (pin "2") (pinfunction "2_2") (pintype "input"))
      (node (ref "U2") (pin "2") (pinfunction "PROG_2") (pintype "input"))
    )
    (net (code "93") (name "Net-(U2-TEMP)") (class "Default")
      (node (ref "R1") (pin "2") (pinfunction "2_2") (pintype "input"))
      (node (ref "R2") (pin "2") (pinfunction "2_2") (pintype "input"))
      (node (ref "R4") (pin "1") (pinfunction "1_1") (pintype "input"))
      (node (ref "U2") (pin "1") (pinfunction "TEMP_1") (pintype "input"))
    )
    (net (code "94") (name "Net-(U3-+IN)") (class "Default")
      (node (ref "C10") (pin "1") (pinfunction "1_1") (pintype "input"))
      (node (ref "U3") (pin "2") (pinfunction "BYPASS_2") (pintype "input"))
      (node (ref "U3") (pin "3") (pinfunction "+IN_3") (pintype "input"))
    )
    (net (code "95") (name "Net-(U3-nSHUTDOWN)") (class "Default")
      (node (ref "R22") (pin "1") (pinfunction "1_1") (pintype "input"))
      (node (ref "U3") (pin "1") (pinfunction "nSHUTDOWN_1") (pintype "input"))
    )
    (net (code "96") (name "Net-(U7-DTR#)") (class "Default")
      (node (ref "R45") (pin "1") (pinfunction "1_1") (pintype "input"))
      (node (ref "U7") (pin "13") (pinfunction "DTR#_13") (pintype "input"))
    )
    (net (code "97") (name "Net-(U7-RTS#)") (class "Default")
      (node (ref "R47") (pin "1") (pinfunction "1_1") (pintype "input"))
      (node (ref "U7") (pin "14") (pinfunction "RTS#_14") (pintype "input"))
      (node (ref "U8") (pin "2") (pinfunction "E_2") (pintype "input"))
    )
    (net (code "98") (name "Net-(U7-V3)") (class "Default")
      (node (ref "C35") (pin "1") (pinfunction "1_1") (pintype "input"))
      (node (ref "U7") (pin "4") (pinfunction "V3_4") (pintype "input"))
    )
    (net (code "99") (name "Net-(U7-XI)") (class "Default")
      (node (ref "C42") (pin "2") (pinfunction "2_2") (pintype "input"))
      (node (ref "U7") (pin "7") (pinfunction "XI_7") (pintype "input"))
      (node (ref "X2") (pin "1") (pinfunction "OSC1_1") (pintype "input"))
    )
    (net (code "100") (name "Net-(U7-XO)") (class "Default")
      (node (ref "C41") (pin "2") (pinfunction "2_2") (pintype "input"))
      (node (ref "U7") (pin "8") (pinfunction "XO_8") (pintype "input"))
      (node (ref "X2") (pin "2") (pinfunction "OSC2_2") (pintype "input"))
    )
    (net (code "101") (name "Net-(U8-B)") (class "Default")
      (node (ref "R45") (pin "2") (pinfunction "2_2") (pintype "input"))
      (node (ref "U8") (pin "1") (pinfunction "B_1") (pintype "input"))
    )
    (net (code "102") (name "ON") (class "Default")
      (node (ref "MCU1") (pin "23") (pinfunction "PA7_23") (pintype "input"))
      (node (ref "R35") (pin "1") (pinfunction "1_1") (pintype "input"))
      (node (ref "TP7") (pin "1") (pinfunction "1_1") (pintype "input"))
    )
    (net (code "103") (name "OSC32_IN") (class "Default")
      (node (ref "C43") (pin "1") (pinfunction "1_1") (pintype "input"))
      (node (ref "MCU1") (pin "3") (pinfunction "PC14-OSC32_IN_3") (pintype "input"))
      (node (ref "X3") (pin "1") (pinfunction "OSC1_1") (pintype "input"))
    )
    (net (code "104") (name "OSC32_OUT") (class "Default")
      (node (ref "C39") (pin "1") (pinfunction "1_1") (pintype "input"))
      (node (ref "MCU1") (pin "4") (pinfunction "PC15-OSC32_OUT_4") (pintype "input"))
      (node (ref "X3") (pin "2") (pinfunction "OSC2_2") (pintype "input"))
    )
    (net (code "105") (name "OSC_IN") (class "Default")
      (node (ref "C33") (pin "1") (pinfunction "1_1") (pintype "input"))
      (node (ref "MCU1") (pin "5") (pinfunction "PDO-OSC_IN_5") (pintype "input"))
      (node (ref "X1") (pin "1") (pinfunction "OSC1_1") (pintype "input"))
    )
    (net (code "106") (name "OSC_OUT") (class "Default")
      (node (ref "C36") (pin "1") (pinfunction "1_1") (pintype "input"))
      (node (ref "MCU1") (pin "6") (pinfunction "PD1-OSC_OUT_6") (pintype "input"))
      (node (ref "X1") (pin "2") (pinfunction "OSC2_2") (pintype "input"))
    )
    (net (code "107") (name "O{slash}F") (class "Default")
      (node (ref "MCU1") (pin "21") (pinfunction "PA5_21") (pintype "input"))
      (node (ref "R40") (pin "2") (pinfunction "2_2") (pintype "input"))
      (node (ref "TP14") (pin "1") (pinfunction "1_1") (pintype "input"))
    )
    (net (code "108") (name "PB4") (class "Default")
      (node (ref "E1") (pin "1") (pinfunction "1_1") (pintype "input"))
      (node (ref "R53") (pin "2") (pinfunction "2_2") (pintype "input"))
      (node (ref "T1") (pin "1") (pinfunction "1_1") (pintype "input"))
    )
    (net (code "109") (name "PB5") (class "Default")
      (node (ref "E2") (pin "1") (pinfunction "1_1") (pintype "input"))
      (node (ref "R54") (pin "2") (pinfunction "2_2") (pintype "input"))
      (node (ref "T1") (pin "2") (pinfunction "2_2") (pintype "input"))
    )
    (net (code "110") (name "PB6") (class "Default")
      (node (ref "E3") (pin "1") (pinfunction "1_1") (pintype "input"))
      (node (ref "R55") (pin "2") (pinfunction "2_2") (pintype "input"))
      (node (ref "T1") (pin "3") (pinfunction "3_3") (pintype "input"))
    )
    (net (code "111") (name "PB7") (class "Default")
      (node (ref "E4") (pin "1") (pinfunction "1_1") (pintype "input"))
      (node (ref "R52") (pin "2") (pinfunction "2_2") (pintype "input"))
      (node (ref "T1") (pin "4") (pinfunction "4_4") (pintype "input"))
    )
    (net (code "112") (name "PB8") (class "Default")
      (node (ref "E5") (pin "1") (pinfunction "1_1") (pintype "input"))
      (node (ref "R50") (pin "2") (pinfunction "2_2") (pintype "input"))
      (node (ref "T1") (pin "5") (pinfunction "5_5") (pintype "input"))
    )
    (net (code "113") (name "PB9") (class "Default")
      (node (ref "E6") (pin "1") (pinfunction "1_1") (pintype "input"))
      (node (ref "R51") (pin "2") (pinfunction "2_2") (pintype "input"))
      (node (ref "T1") (pin "6") (pinfunction "6_6") (pintype "input"))
    )
    (net (code "114") (name "RESET") (class "Default")
      (node (ref "C40") (pin "2") (pinfunction "2_2") (pintype "input"))
      (node (ref "D6") (pin "2") (pinfunction "A_2") (pintype "input"))
      (node (ref "Krest") (pin "1") (pinfunction "1_1") (pintype "input"))
      (node (ref "MCU1") (pin "7") (pinfunction "NRST_7") (pintype "input"))
      (node (ref "R46") (pin "1") (pinfunction "1_1") (pintype "input"))
    )
    (net (code "115") (name "RGB_B_CTL") (class "Default")
      (node (ref "MCU1") (pin "45") (pinfunction "PA12_45") (pintype "input"))
      (node (ref "R56") (pin "1") (pinfunction "1_1") (pintype "input"))
    )
    (net (code "116") (name "RGB_G_CTL") (class "Default")
      (node (ref "MCU1") (pin "44") (pinfunction "PA11_44") (pintype "input"))
      (node (ref "R57") (pin "1") (pinfunction "1_1") (pintype "input"))
    )
    (net (code "117") (name "RGB_R_CTL") (class "Default")
      (node (ref "MCU1") (pin "41") (pinfunction "PA8_41") (pintype "input"))
      (node (ref "R58") (pin "1") (pinfunction "1_1") (pintype "input"))
    )
    (net (code "118") (name "RIGHT_Q") (class "Default")
      (node (ref "MCU1") (pin "24") (pinfunction "PC4_24") (pintype "input"))
      (node (ref "R5") (pin "1") (pinfunction "1_1") (pintype "input"))
    )
    (net (code "119") (name "RIGHT_Z") (class "Default")
      (node (ref "MCU1") (pin "25") (pinfunction "PC5_25") (pintype "input"))
      (node (ref "R6") (pin "1") (pinfunction "1_1") (pintype "input"))
    )
    (net (code "120") (name "STDBY") (class "Default")
      (node (ref "R10") (pin "1") (pinfunction "1_1") (pintype "input"))
      (node (ref "U2") (pin "6") (pinfunction "STDBY#_6") (pintype "input"))
    )
    (net (code "121") (name "SWCLK") (class "Default")
      (node (ref "E10") (pin "1") (pinfunction "1_1") (pintype "input"))
      (node (ref "H4") (pin "4") (pinfunction "4_4") (pintype "input"))
      (node (ref "R71") (pin "2") (pinfunction "2_2") (pintype "input"))
    )
    (net (code "122") (name "SWDIO") (class "Default")
      (node (ref "E9") (pin "1") (pinfunction "1_1") (pintype "input"))
      (node (ref "H4") (pin "3") (pinfunction "3_3") (pintype "input"))
      (node (ref "R72") (pin "2") (pinfunction "2_2") (pintype "input"))
    )
    (net (code "123") (name "TFT_O{slash}F") (class "Default")
      (node (ref "MCU1") (pin "54") (pinfunction "PD2_54") (pintype "input"))
      (node (ref "R77") (pin "1") (pinfunction "1_1") (pintype "input"))
    )
    (net (code "124") (name "U1_RXD") (class "Default")
      (node (ref "MCU1") (pin "43") (pinfunction "PA10_43") (pintype "input"))
      (node (ref "U7") (pin "2") (pinfunction "TXD_2") (pintype "input"))
    )
    (net (code "125") (name "U1_TXD") (class "Default")
      (node (ref "MCU1") (pin "42") (pinfunction "PA9_42") (pintype "input"))
      (node (ref "U7") (pin "3") (pinfunction "RXD_3") (pintype "input"))
    )
    (net (code "126") (name "VBAT_SYS") (class "Default")
      (node (ref "C15") (pin "2") (pinfunction "2_2") (pintype "input"))
      (node (ref "C17") (pin "1") (pinfunction "1_1") (pintype "input"))
      (node (ref "C18") (pin "2") (pinfunction "2_2") (pintype "input"))
      (node (ref "C21") (pin "1") (pinfunction "1_1") (pintype "input"))
      (node (ref "C22") (pin "2") (pinfunction "2_2") (pintype "input"))
      (node (ref "C28") (pin "1") (pinfunction "1_1") (pintype "input"))
      (node (ref "C29") (pin "2") (pinfunction "2_2") (pintype "input"))
      (node (ref "Q5") (pin "3") (pinfunction "D_3") (pintype "input"))
      (node (ref "TP6") (pin "1") (pinfunction "1_1") (pintype "input"))
      (node (ref "U4") (pin "1") (pinfunction "VIN_1") (pintype "input"))
      (node (ref "U4") (pin "3") (pinfunction "EN_3") (pintype "input"))
      (node (ref "U5") (pin "1") (pinfunction "VIN_1") (pintype "input"))
      (node (ref "U5") (pin "3") (pinfunction "EN_3") (pintype "input"))
      (node (ref "U6") (pin "1") (pinfunction "VIN_1") (pintype "input"))
      (node (ref "U6") (pin "3") (pinfunction "EN_3") (pintype "input"))
    )
    (net (code "127") (name "VBUS_5V") (class "Default")
      (node (ref "C3") (pin "1") (pinfunction "1_1") (pintype "input"))
      (node (ref "C32") (pin "1") (pinfunction "1_1") (pintype "input"))
      (node (ref "C34") (pin "1") (pinfunction "1_1") (pintype "input"))
      (node (ref "C4") (pin "1") (pinfunction "1_1") (pintype "input"))
      (node (ref "LED1") (pin "1") (pinfunction "A_1") (pintype "input"))
      (node (ref "LED2") (pin "2") (pinfunction "A_2") (pintype "input"))
      (node (ref "R2") (pin "1") (pinfunction "1_1") (pintype "input"))
      (node (ref "R8") (pin "2") (pinfunction "2_2") (pintype "input"))
      (node (ref "U1") (pin "2") (pinfunction "2_2") (pintype "input"))
      (node (ref "U2") (pin "4") (pinfunction "VCC_4") (pintype "input"))
      (node (ref "U7") (pin "16") (pinfunction "VCC_16") (pintype "input"))
    )
    (net (code "128") (name "VCC_3V3") (class "Default")
      (node (ref "3V2") (pin "1") (pinfunction "1_1") (pintype "input"))
      (node (ref "C19") (pin "2") (pinfunction "2_2") (pintype "input"))
      (node (ref "C20") (pin "1") (pinfunction "1_1") (pintype "input"))
      (node (ref "C37") (pin "2") (pinfunction "2_2") (pintype "input"))
      (node (ref "C38") (pin "2") (pinfunction "2_2") (pintype "input"))
      (node (ref "C53") (pin "2") (pinfunction "2_2") (pintype "input"))
      (node (ref "C54") (pin "2") (pinfunction "2_2") (pintype "input"))
      (node (ref "C55") (pin "2") (pinfunction "2_2") (pintype "input"))
      (node (ref "C56") (pin "2") (pinfunction "2_2") (pintype "input"))
      (node (ref "C57") (pin "1") (pinfunction "1_1") (pintype "input"))
      (node (ref "D7") (pin "1") (pinfunction "A_1") (pintype "input"))
      (node (ref "D8") (pin "1") (pinfunction "A_1") (pintype "input"))
      (node (ref "H4") (pin "1") (pinfunction "1_1") (pintype "input"))
      (node (ref "I1") (pin "8") (pinfunction "8_8") (pintype "input"))
      (node (ref "LED10") (pin "1") (pinfunction "A_1") (pintype "input"))
      (node (ref "LED6") (pin "3") (pinfunction "3_3") (pintype "input"))
      (node (ref "LED7") (pin "1") (pinfunction "A_1") (pintype "input"))
      (node (ref "LED8") (pin "1") (pinfunction "A_1") (pintype "input"))
      (node (ref "LED9") (pin "1") (pinfunction "A_1") (pintype "input"))
      (node (ref "MCU1") (pin "13") (pinfunction "VDDA_13") (pintype "input"))
      (node (ref "MCU1") (pin "19") (pinfunction "VDD_4_19") (pintype "input"))
      (node (ref "MCU1") (pin "32") (pinfunction "VDD_1_32") (pintype "input"))
      (node (ref "MCU1") (pin "48") (pinfunction "VDD_2_48") (pintype "input"))
      (node (ref "MCU1") (pin "64") (pinfunction "VDD_3_64") (pintype "input"))
      (node (ref "Q8") (pin "2") (pinfunction "E_2") (pintype "input"))
      (node (ref "Q9") (pin "2") (pinfunction "S_2") (pintype "input"))
      (node (ref "R3") (pin "1") (pinfunction "1_1") (pintype "input"))
      (node (ref "R31") (pin "2") (pinfunction "2_2") (pintype "input"))
      (node (ref "R33") (pin "2") (pinfunction "2_2") (pintype "input"))
      (node (ref "R44") (pin "2") (pinfunction "2_2") (pintype "input"))
      (node (ref "R46") (pin "2") (pinfunction "2_2") (pintype "input"))
      (node (ref "R63") (pin "2") (pinfunction "2_2") (pintype "input"))
      (node (ref "R64") (pin "2") (pinfunction "2_2") (pintype "input"))
      (node (ref "R65") (pin "2") (pinfunction "2_2") (pintype "input"))
      (node (ref "R66") (pin "2") (pinfunction "2_2") (pintype "input"))
      (node (ref "R67") (pin "2") (pinfunction "2_2") (pintype "input"))
      (node (ref "R68") (pin "2") (pinfunction "2_2") (pintype "input"))
      (node (ref "R75") (pin "1") (pinfunction "1_1") (pintype "input"))
      (node (ref "SW1") (pin "(1)") (pinfunction "(1)_(1)") (pintype "input"))
      (node (ref "SW1") (pin "1") (pinfunction "1_1") (pintype "input"))
      (node (ref "SW2") (pin "(1)") (pinfunction "(1)_(1)") (pintype "input"))
      (node (ref "SW2") (pin "1") (pinfunction "1_1") (pintype "input"))
      (node (ref "U4") (pin "5") (pinfunction "VOUT_5") (pintype "input"))
    )
    (net (code "129") (name "VCC_3V3_1") (class "Default")
      (node (ref "3V3_1") (pin "1") (pinfunction "1_1") (pintype "input"))
      (node (ref "C11") (pin "1") (pinfunction "1_1") (pintype "input"))
      (node (ref "C23") (pin "2") (pinfunction "2_2") (pintype "input"))
      (node (ref "C24") (pin "1") (pinfunction "1_1") (pintype "input"))
      (node (ref "C6") (pin "1") (pinfunction "1_1") (pintype "input"))
      (node (ref "Q1") (pin "2") (pinfunction "S_2") (pintype "input"))
      (node (ref "Q3") (pin "2") (pinfunction "S_2") (pintype "input"))
      (node (ref "R16") (pin "2") (pinfunction "2_2") (pintype "input"))
      (node (ref "R24") (pin "2") (pinfunction "2_2") (pintype "input"))
      (node (ref "R38") (pin "2") (pinfunction "2_2") (pintype "input"))
      (node (ref "U5") (pin "5") (pinfunction "VOUT_5") (pintype "input"))
    )
    (net (code "130") (name "VCC_3V3_2") (class "Default")
      (node (ref "3V1") (pin "1") (pinfunction "1_1") (pintype "input"))
      (node (ref "3V3_2") (pin "1") (pinfunction "1_1") (pintype "input"))
      (node (ref "C30") (pin "2") (pinfunction "2_2") (pintype "input"))
      (node (ref "C31") (pin "1") (pinfunction "1_1") (pintype "input"))
      (node (ref "C8") (pin "1") (pinfunction "1_1") (pintype "input"))
      (node (ref "C9") (pin "2") (pinfunction "2_2") (pintype "input"))
      (node (ref "R22") (pin "2") (pinfunction "2_2") (pintype "input"))
      (node (ref "R43") (pin "2") (pinfunction "2_2") (pintype "input"))
      (node (ref "U3") (pin "6") (pinfunction "VDD_6") (pintype "input"))
      (node (ref "U6") (pin "5") (pinfunction "VOUT_5") (pintype "input"))
    )
    (net (code "131") (name "VCC_TFT") (class "Default")
      (node (ref "C44") (pin "2") (pinfunction "2_2") (pintype "input"))
      (node (ref "C51") (pin "2") (pinfunction "2_2") (pintype "input"))
      (node (ref "C52") (pin "2") (pinfunction "2_2") (pintype "input"))
      (node (ref "D10") (pin "1") (pinfunction "A_1") (pintype "input"))
      (node (ref "D9") (pin "1") (pinfunction "A_1") (pintype "input"))
      (node (ref "Q9") (pin "3") (pinfunction "D_3") (pintype "input"))
      (node (ref "T1") (pin "8") (pinfunction "8_8") (pintype "input"))
      (node (ref "U9") (pin "2") (pinfunction "2_2") (pintype "unspecified"))
    )
    (net (code "132") (name "VO1") (class "Default")
      (node (ref "H1") (pin "2") (pinfunction "2_2") (pintype "input"))
      (node (ref "R15") (pin "1") (pinfunction "1_1") (pintype "input"))
      (node (ref "TP3") (pin "1") (pinfunction "1_1") (pintype "input"))
      (node (ref "U3") (pin "5") (pinfunction "Vo1_5") (pintype "input"))
    )
    (net (code "133") (name "VO2") (class "Default")
      (node (ref "H1") (pin "1") (pinfunction "1_1") (pintype "input"))
      (node (ref "TP2") (pin "1") (pinfunction "1_1") (pintype "input"))
      (node (ref "U3") (pin "8") (pinfunction "Vo2_8") (pintype "input"))
    )
    (net (code "134") (name "WIRE_RX") (class "Default")
      (node (ref "E7") (pin "1") (pinfunction "1_1") (pintype "input"))
      (node (ref "R69") (pin "2") (pinfunction "2_2") (pintype "input"))
      (node (ref "U9") (pin "6") (pinfunction "6_6") (pintype "unspecified"))
    )
    (net (code "135") (name "WIRE_TX") (class "Default")
      (node (ref "E8") (pin "1") (pinfunction "1_1") (pintype "input"))
      (node (ref "R70") (pin "2") (pinfunction "2_2") (pintype "input"))
      (node (ref "U9") (pin "8") (pinfunction "8_8") (pintype "unspecified"))
    )
    (net (code "136") (name "YIN_PIN") (class "Default")
      (node (ref "C5") (pin "2") (pinfunction "2_2") (pintype "input"))
      (node (ref "MCU1") (pin "20") (pinfunction "PA4_20") (pintype "input"))
      (node (ref "TP4") (pin "1") (pinfunction "1_1") (pintype "input"))
    )
    (net (code "137") (name "unconnected-(I1-Pad1)") (class "Default")
      (node (ref "I1") (pin "1") (pinfunction "1_1") (pintype "input+no_connect"))
    )
    (net (code "138") (name "unconnected-(I1-Pad2)") (class "Default")
      (node (ref "I1") (pin "2") (pinfunction "2_2") (pintype "input+no_connect"))
    )
    (net (code "139") (name "unconnected-(I1-Pad3)") (class "Default")
      (node (ref "I1") (pin "3") (pinfunction "3_3") (pintype "input+no_connect"))
    )
    (net (code "140") (name "unconnected-(I1-Pad4)") (class "Default")
      (node (ref "I1") (pin "4") (pinfunction "4_4") (pintype "input+no_connect"))
    )
    (net (code "141") (name "unconnected-(R15-Pad3)") (class "Default")
      (node (ref "R15") (pin "3") (pinfunction "3_3") (pintype "input+no_connect"))
    )
    (net (code "142") (name "unconnected-(U4-NC-Pad4)") (class "Default")
      (node (ref "U4") (pin "4") (pinfunction "NC_4") (pintype "input+no_connect"))
    )
    (net (code "143") (name "unconnected-(U5-NC-Pad4)") (class "Default")
      (node (ref "U5") (pin "4") (pinfunction "NC_4") (pintype "input+no_connect"))
    )
    (net (code "144") (name "unconnected-(U6-NC-Pad4)") (class "Default")
      (node (ref "U6") (pin "4") (pinfunction "NC_4") (pintype "input+no_connect"))
    )
    (net (code "145") (name "unconnected-(U7-CTS#-Pad9)") (class "Default")
      (node (ref "U7") (pin "9") (pinfunction "CTS#_9") (pintype "input+no_connect"))
    )
    (net (code "146") (name "unconnected-(U7-DCD#-Pad12)") (class "Default")
      (node (ref "U7") (pin "12") (pinfunction "DCD#_12") (pintype "input+no_connect"))
    )
    (net (code "147") (name "unconnected-(U7-DSR#-Pad10)") (class "Default")
      (node (ref "U7") (pin "10") (pinfunction "DSR#_10") (pintype "input+no_connect"))
    )
    (net (code "148") (name "unconnected-(U7-R232-Pad15)") (class "Default")
      (node (ref "U7") (pin "15") (pinfunction "R232_15") (pintype "input+no_connect"))
    )
    (net (code "149") (name "unconnected-(U7-RI#-Pad11)") (class "Default")
      (node (ref "U7") (pin "11") (pinfunction "RI#_11") (pintype "input+no_connect"))
    )
    (net (code "150") (name "unconnected-(U9-Pad1)") (class "Default")
      (node (ref "U9") (pin "1") (pinfunction "1_1") (pintype "unspecified+no_connect"))
    )
    (net (code "151") (name "unconnected-(U9-Pad3)") (class "Default")
      (node (ref "U9") (pin "3") (pinfunction "3_3") (pintype "unspecified+no_connect"))
    )
    (net (code "152") (name "unconnected-(U9-Pad5)") (class "Default")
      (node (ref "U9") (pin "5") (pinfunction "5_5") (pintype "unspecified+no_connect"))
    )
    (net (code "153") (name "unconnected-(U9-Pad7)") (class "Default")
      (node (ref "U9") (pin "7") (pinfunction "7_7") (pintype "unspecified+no_connect"))
    )
    (net (code "154") (name "unconnected-(USB1-ID-Pad4)") (class "Default")
      (node (ref "USB1") (pin "4") (pinfunction "ID_4") (pintype "input+no_connect"))
    )
    (net (code "155") (name "unconnected-(开关-Pad2)") (class "Default")
      (node (ref "开关") (pin "2") (pinfunction "2_2") (pintype "input+no_connect"))
    )
    (net (code "156") (name "unconnected-(开关-Pad3)") (class "Default")
      (node (ref "开关") (pin "3") (pinfunction "3_3") (pintype "input+no_connect"))
    )
  )
)
